# tottag.net
KiCad netlist of a schematic drawn in EAGLE
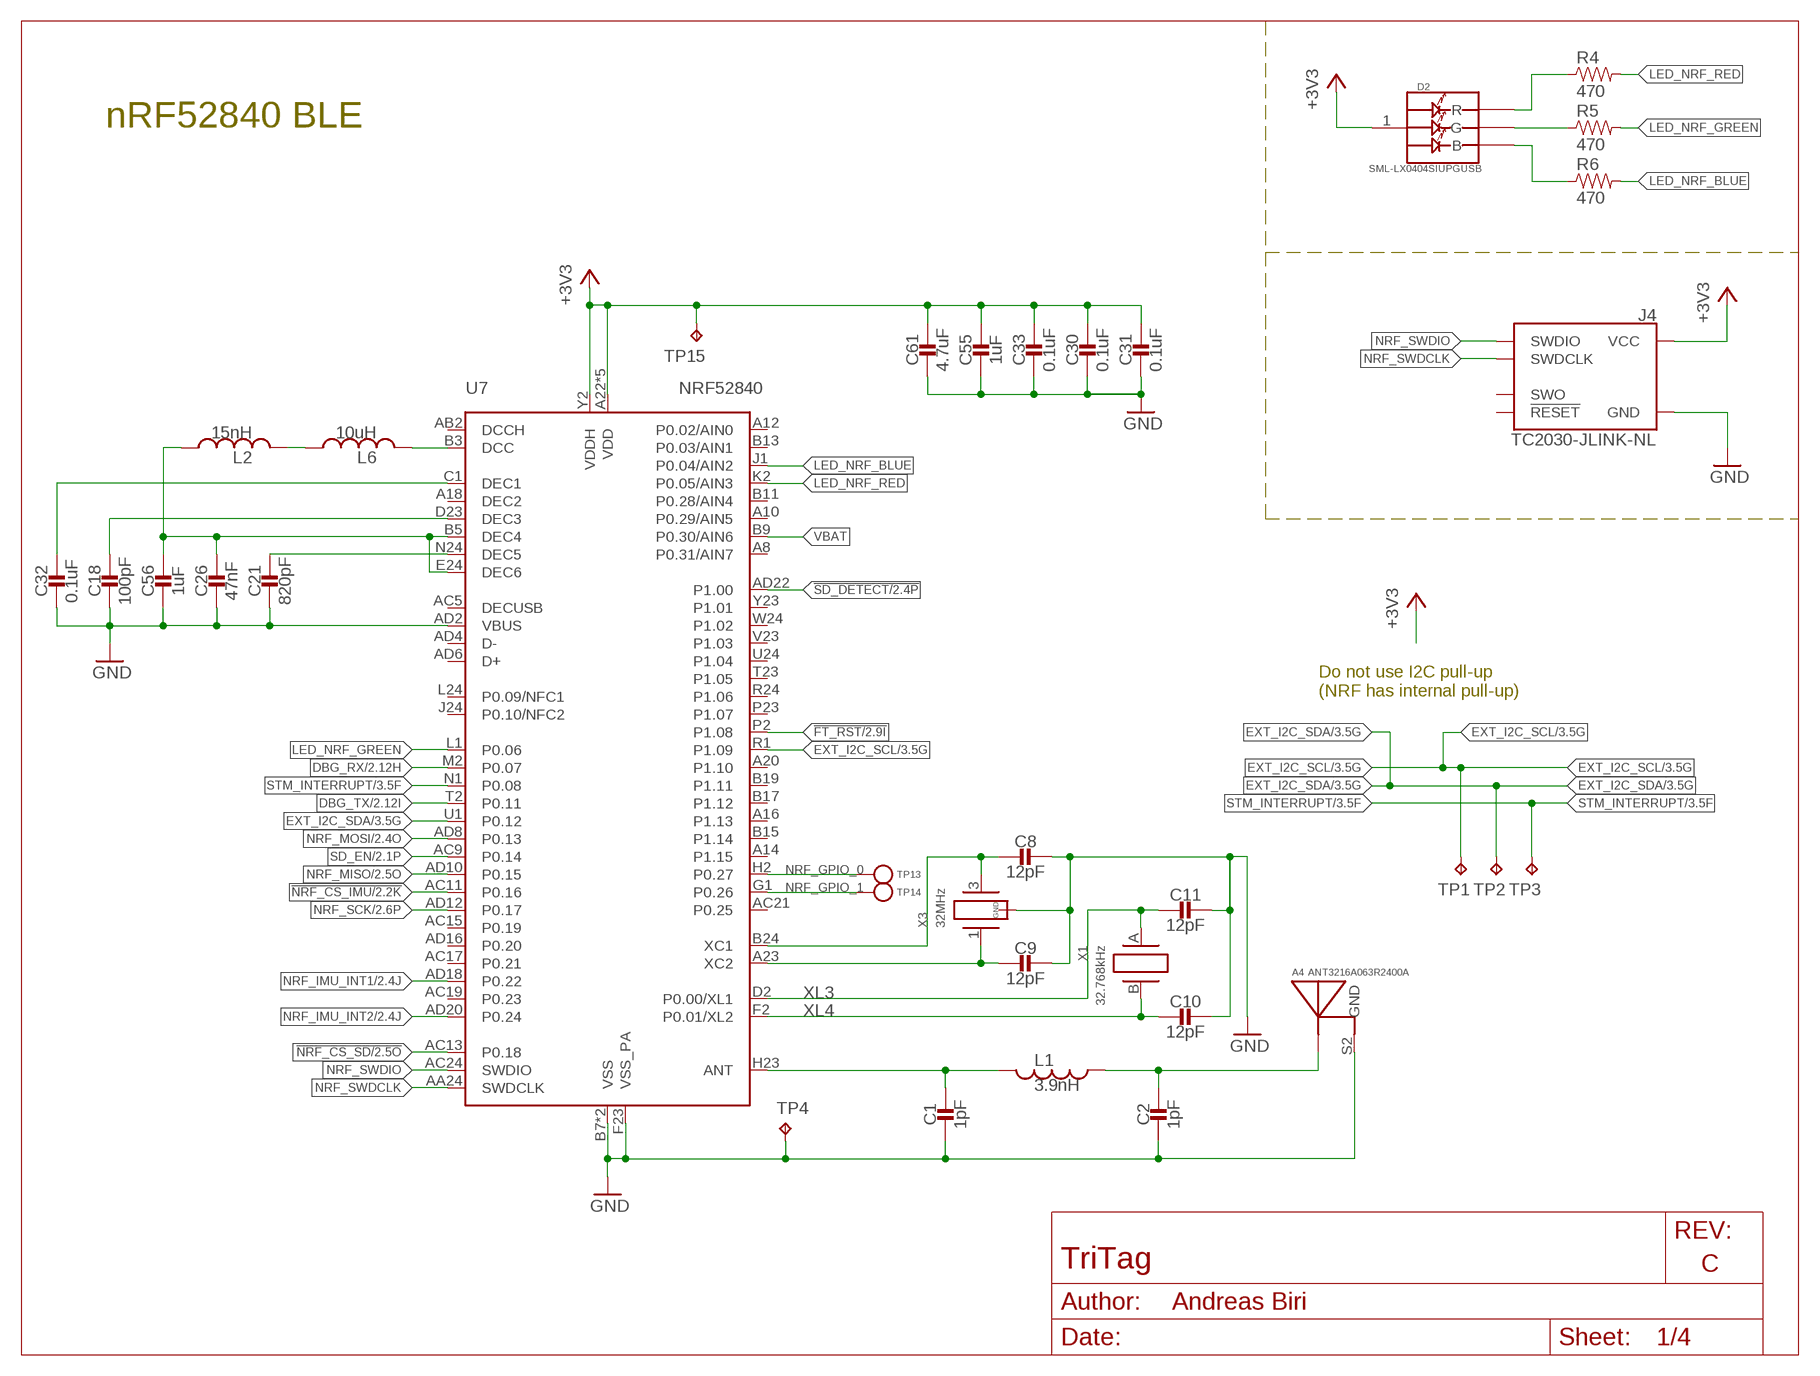
[diagram p0: schematic, sheet 1]
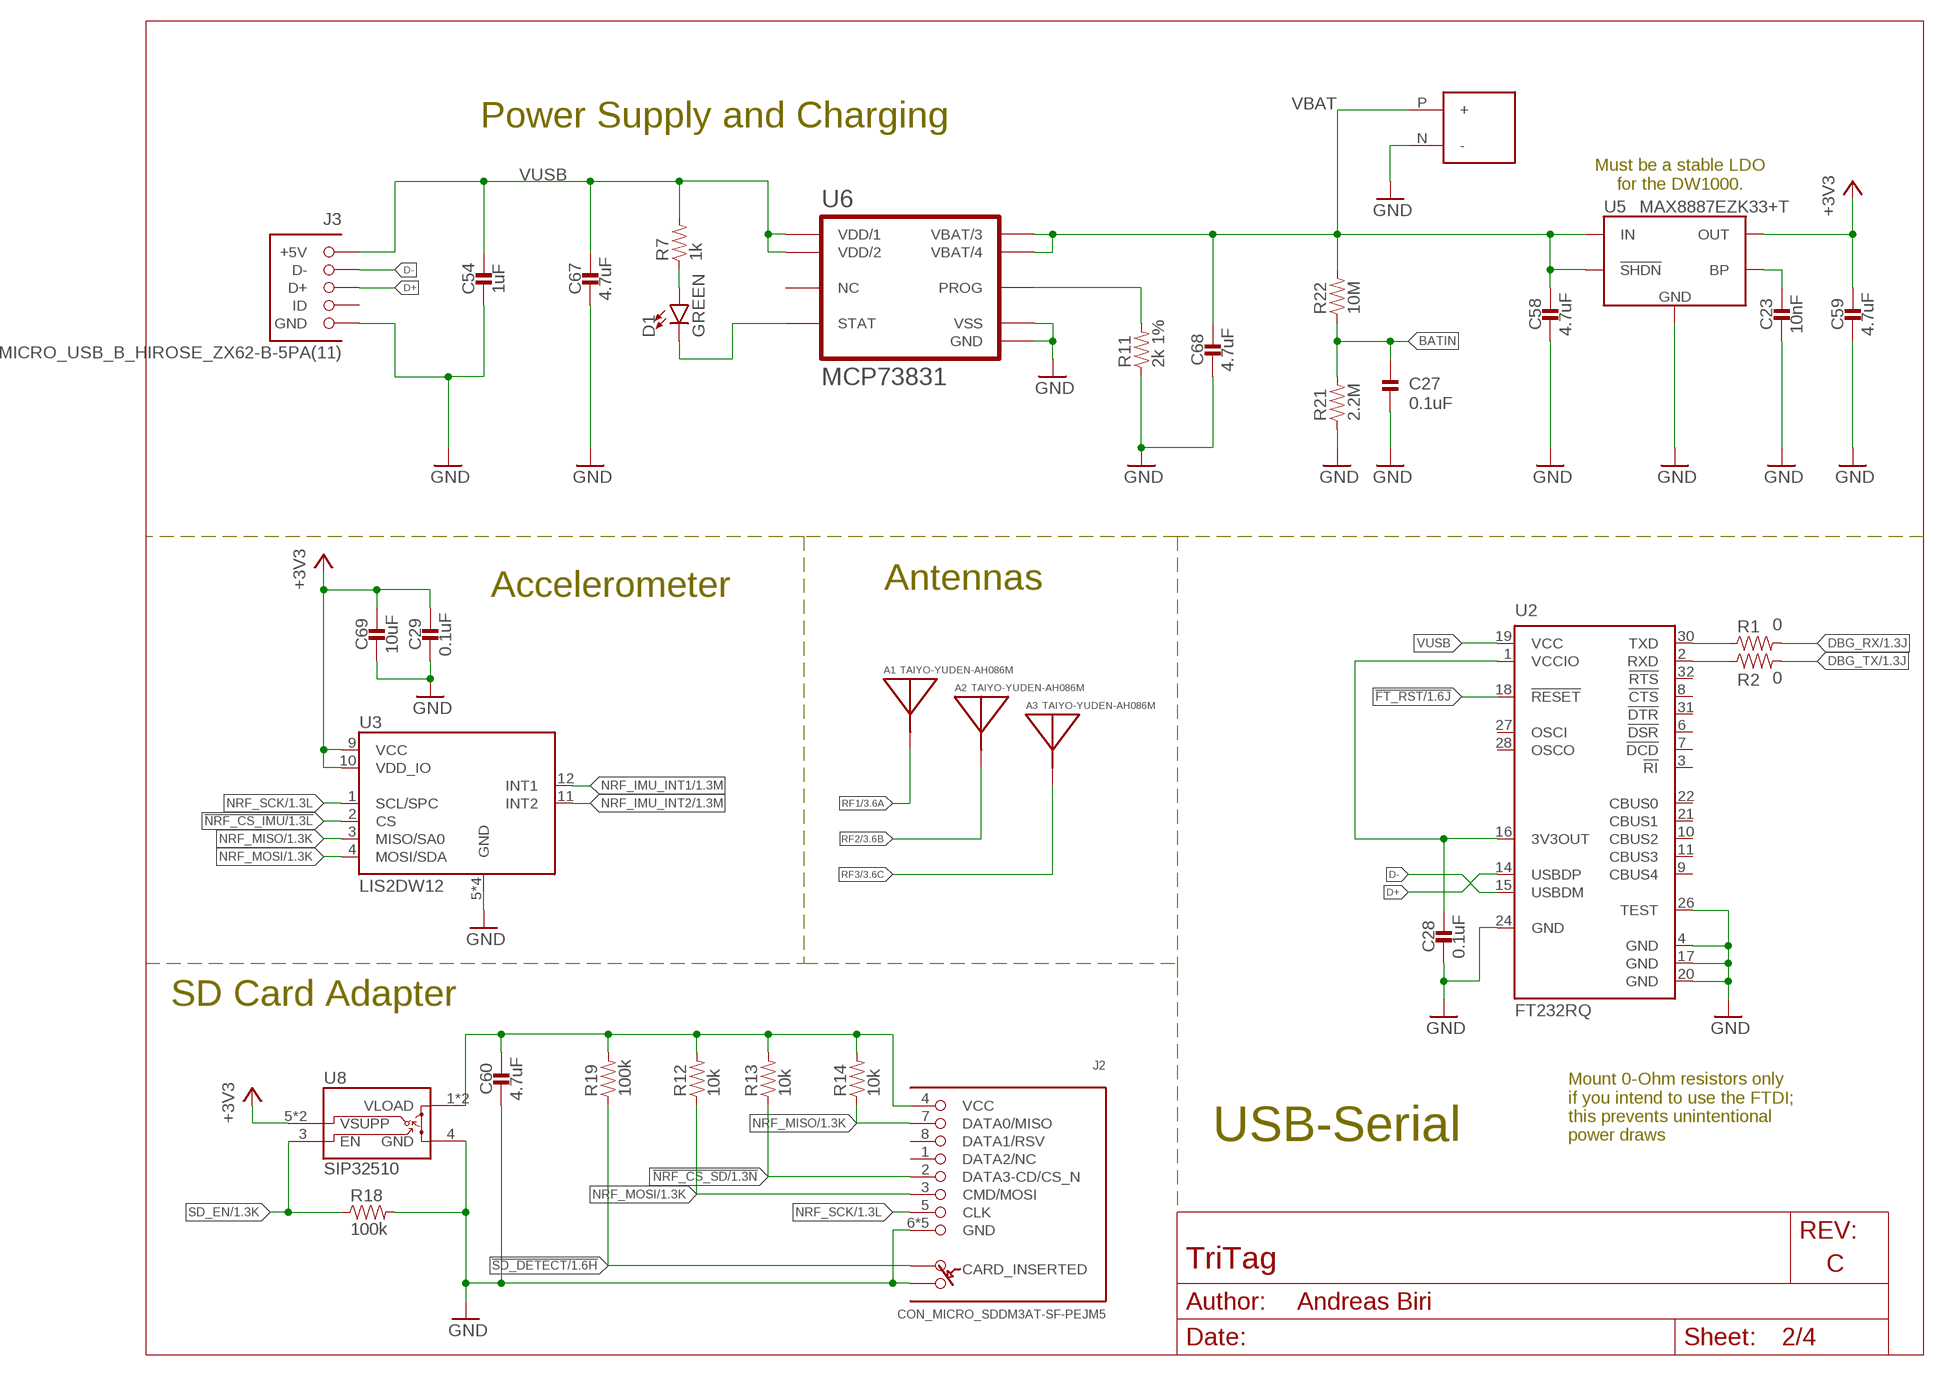
[diagram p1: schematic, sheet 2]
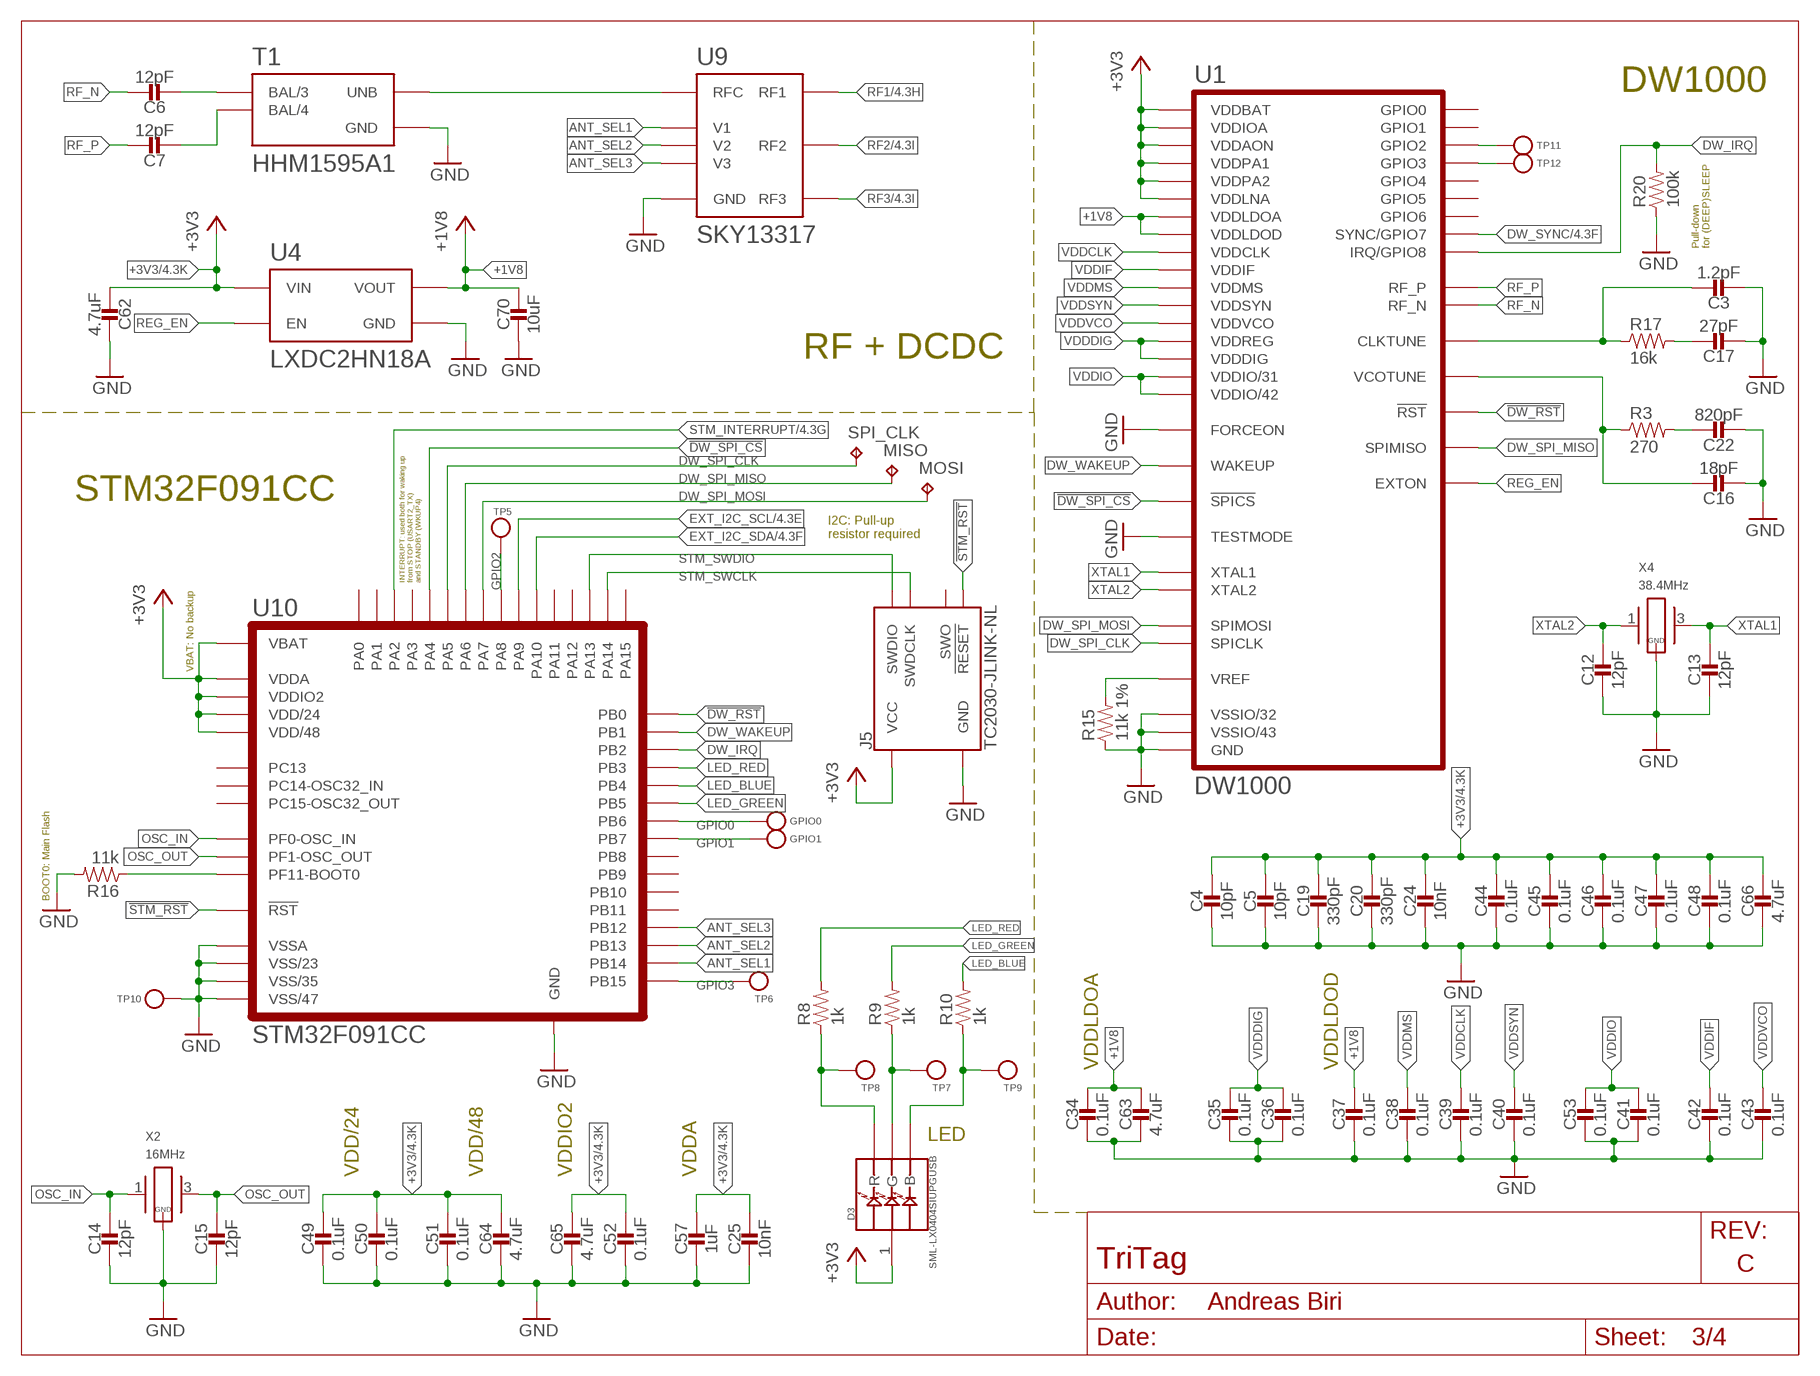
[diagram p2: schematic, sheet 3]
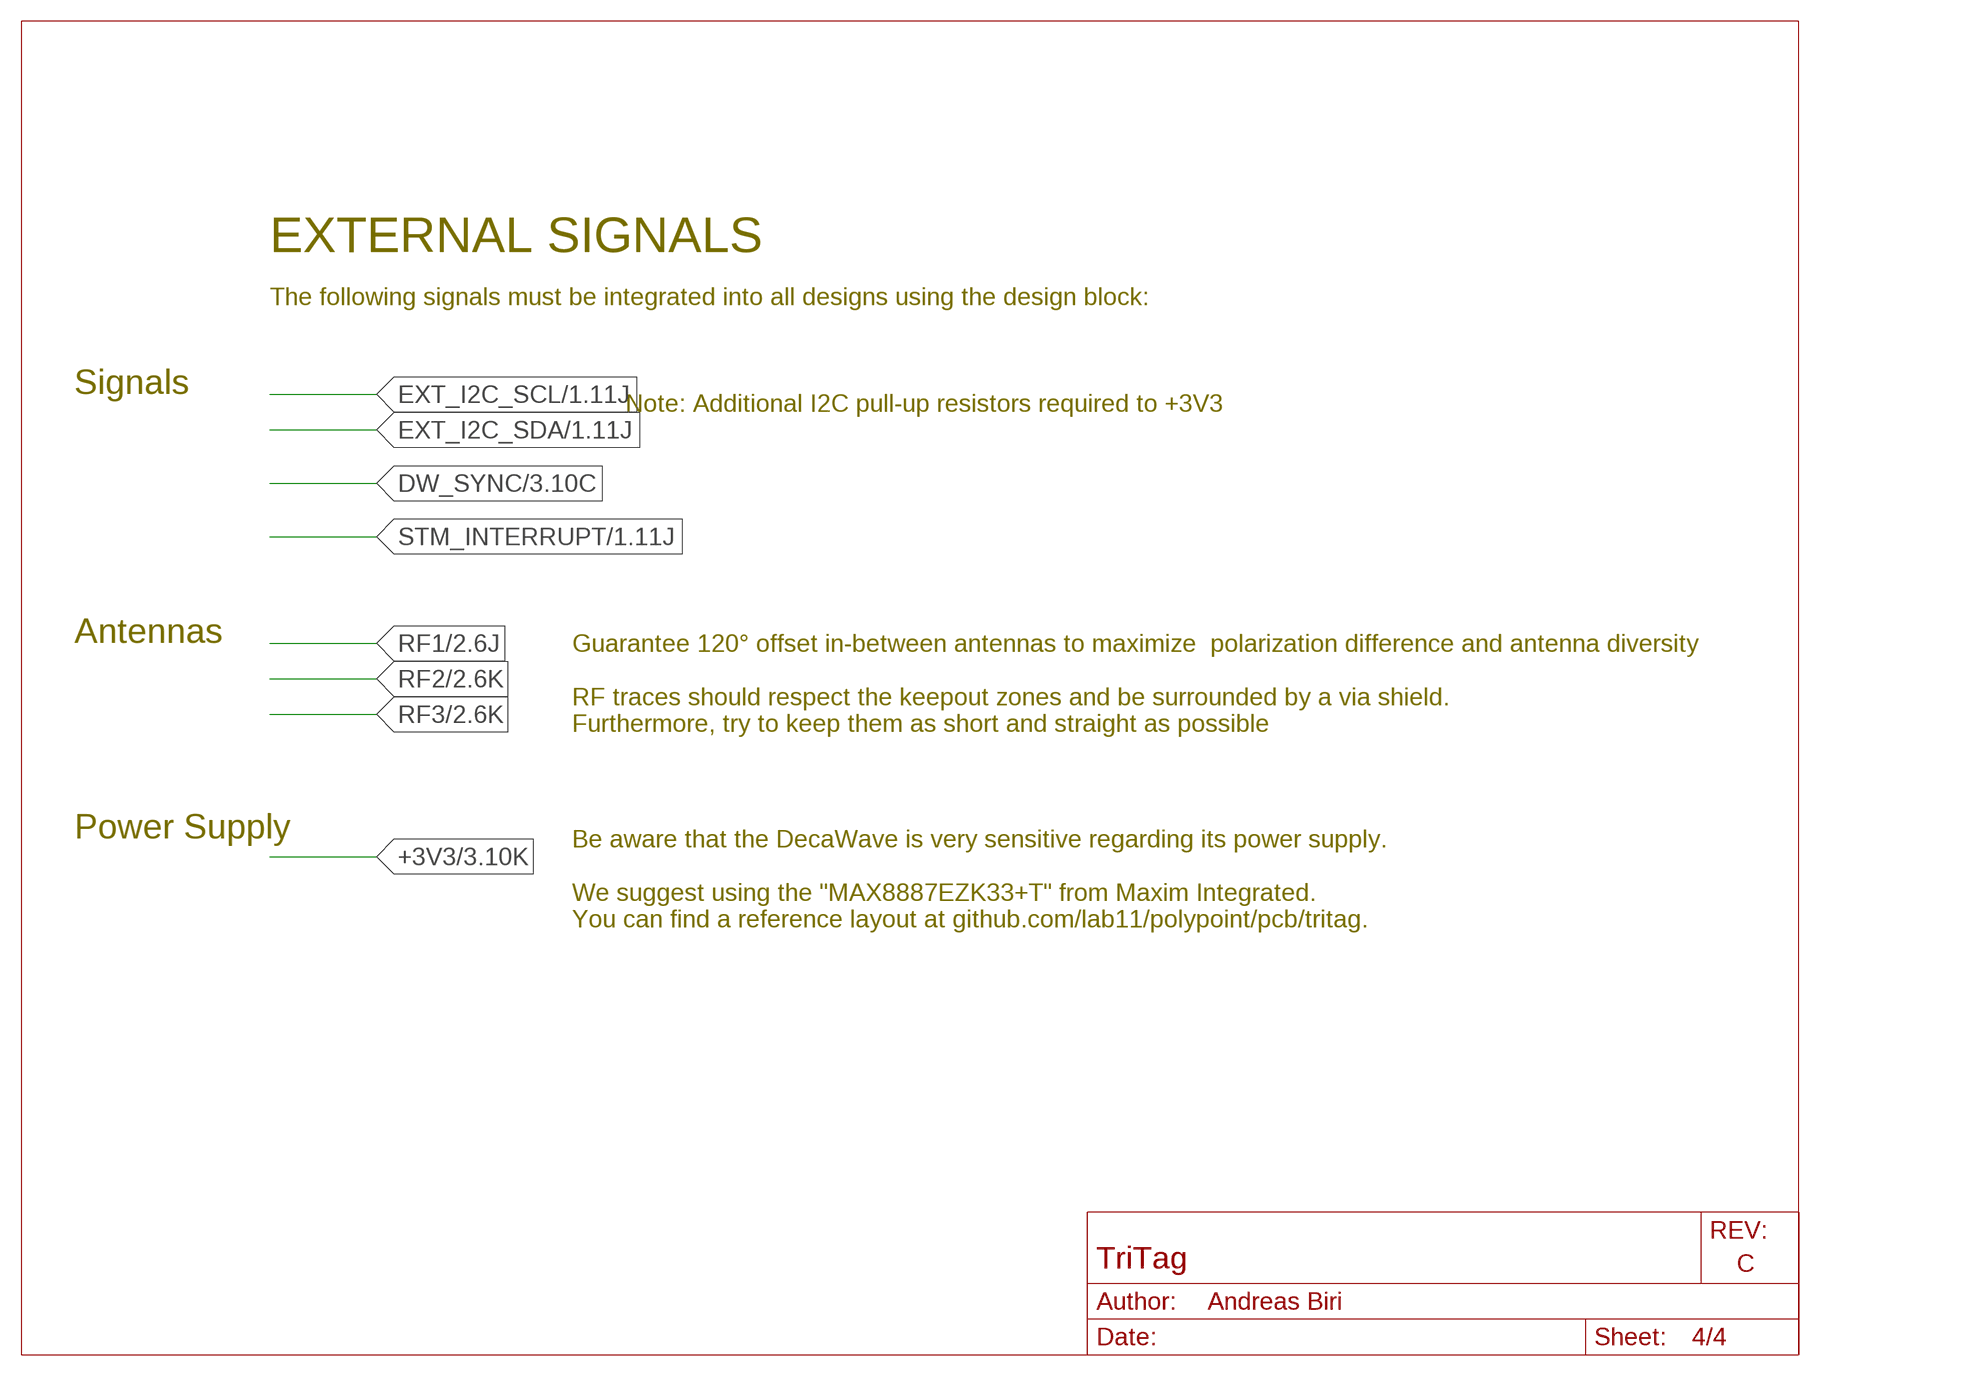
[diagram p3: schematic, sheet 4]

(export (version "E")
  (design (tool "Eeschema 10.0.6"))
  (components
    (comp (ref "A4")
      (value "ANT3216A063R2400A")
      (footprint "eagle-import:ANT3216A063R2400A")
      (fields (field (name "MANUFACTURER") "YAGEO"))
      (libsource (lib "eagle-import") (part "ANT3216A063R2400A"))
    )
    (comp (ref "C1")
      (value "1pF")
      (footprint "eagle-import:0402_CAP")
      (fields (field (name "MPN") "GJM1555C1H1R0CB01D "))
      (libsource (lib "eagle-import") (part "CAPACITOR0402_CAP"))
    )
    (comp (ref "C2")
      (value "1pF")
      (footprint "eagle-import:0402_CAP")
      (fields (field (name "MPN") "GJM1555C1H1R0CB01D"))
      (libsource (lib "eagle-import") (part "CAPACITOR0402_CAP"))
    )
    (comp (ref "C8")
      (value "12pF")
      (footprint "eagle-import:0402_CAP")
      (fields (field (name "MPN") "GRM1555C1H120GA01D "))
      (libsource (lib "eagle-import") (part "CAPACITOR0402_CAP"))
    )
    (comp (ref "C9")
      (value "12pF")
      (footprint "eagle-import:0402_CAP")
      (fields (field (name "MPN") "GRM1555C1H120GA01D "))
      (libsource (lib "eagle-import") (part "CAPACITOR0402_CAP"))
    )
    (comp (ref "C10")
      (value "12pF")
      (footprint "eagle-import:0402_CAP")
      (fields (field (name "MPN") "GRM1555C1H120GA01D "))
      (libsource (lib "eagle-import") (part "CAPACITOR0402_CAP"))
    )
    (comp (ref "C11")
      (value "12pF")
      (footprint "eagle-import:0402_CAP")
      (fields (field (name "MPN") "GRM1555C1H120GA01D "))
      (libsource (lib "eagle-import") (part "CAPACITOR0402_CAP"))
    )
    (comp (ref "C18")
      (value "100pF")
      (footprint "eagle-import:0402_CAP")
      (fields (field (name "MPN") "GRM1555C1H101JA01D "))
      (libsource (lib "eagle-import") (part "CAPACITOR0402_CAP"))
    )
    (comp (ref "C21")
      (value "820pF")
      (footprint "eagle-import:0402_CAP")
      (fields (field (name "MPN") "CL05C821JB5NFNC"))
      (libsource (lib "eagle-import") (part "CAPACITOR0402_CAP"))
    )
    (comp (ref "C26")
      (value "47nF")
      (footprint "eagle-import:0402_CAP")
      (fields (field (name "MPN") "C1005X7R1C473K050BC "))
      (libsource (lib "eagle-import") (part "CAPACITOR0402_CAP"))
    )
    (comp (ref "C30")
      (value "0.1uF")
      (footprint "eagle-import:0402_CAP")
      (fields (field (name "MPN") "GRM155R71C104KA88J "))
      (libsource (lib "eagle-import") (part "CAPACITOR0402_CAP"))
    )
    (comp (ref "C31")
      (value "0.1uF")
      (footprint "eagle-import:0402_CAP")
      (fields (field (name "MPN") "GRM155R71C104KA88J "))
      (libsource (lib "eagle-import") (part "CAPACITOR0402_CAP"))
    )
    (comp (ref "C32")
      (value "0.1uF")
      (footprint "eagle-import:0402_CAP")
      (fields (field (name "MPN") "GRM155R71C104KA88J "))
      (libsource (lib "eagle-import") (part "CAPACITOR0402_CAP"))
    )
    (comp (ref "C33")
      (value "0.1uF")
      (footprint "eagle-import:0402_CAP")
      (fields (field (name "MPN") "GRM155R71C104KA88J "))
      (libsource (lib "eagle-import") (part "CAPACITOR0402_CAP"))
    )
    (comp (ref "C55")
      (value "1uF")
      (footprint "eagle-import:0402_CAP")
      (fields (field (name "MPN") "GRM155R70G105KA12D "))
      (libsource (lib "eagle-import") (part "CAPACITOR0402_CAP"))
    )
    (comp (ref "C56")
      (value "1uF")
      (footprint "eagle-import:0402_CAP")
      (fields (field (name "MPN") "GRM155R70G105KA12D "))
      (libsource (lib "eagle-import") (part "CAPACITOR0402_CAP"))
    )
    (comp (ref "C61")
      (value "4.7uF")
      (footprint "eagle-import:0402_CAP")
      (fields (field (name "MPN") "C1005X5R0J475K050BC "))
      (libsource (lib "eagle-import") (part "CAPACITOR0402_CAP"))
    )
    (comp (ref "D2")
      (value "SML-LX0404SIUPGUSB")
      (footprint "eagle-import:1MM_SQ_4PAD")
      (fields (field (name "MANUFACTURER") "Lumex Opto"))
      (libsource (lib "eagle-import") (part "SML-LX0404SIUPGUSB"))
    )
    (comp (ref "J4")
      (value "TC2030-JLINK-NL")
      (footprint "eagle-import:TC2030-IDC-NL")
      (libsource (lib "eagle-import") (part "TC2030-JLINK-NL"))
    )
    (comp (ref "L1")
      (value "3.9nH")
      (footprint "eagle-import:0402_CAP")
      (fields (field (name "MPN") "AISC-0402-3N9G-T "))
      (libsource (lib "eagle-import") (part "INDUCTOR0402"))
    )
    (comp (ref "L2")
      (value "15nH")
      (footprint "eagle-import:0402_CAP")
      (fields (field (name "MPN") "HK100515NJ-T "))
      (libsource (lib "eagle-import") (part "INDUCTOR0402"))
    )
    (comp (ref "L6")
      (value "10uH")
      (footprint "eagle-import:0603_CAP")
      (fields (field (name "MPN") "LQM18FN100M00D "))
      (libsource (lib "eagle-import") (part "INDUCTOR0603"))
    )
    (comp (ref "R4")
      (value "470")
      (footprint "eagle-import:0402_RES")
      (libsource (lib "eagle-import") (part "RESISTOR0402_RES"))
    )
    (comp (ref "R5")
      (value "470")
      (footprint "eagle-import:0402_RES")
      (libsource (lib "eagle-import") (part "RESISTOR0402_RES"))
    )
    (comp (ref "R6")
      (value "470")
      (footprint "eagle-import:0402_RES")
      (libsource (lib "eagle-import") (part "RESISTOR0402_RES"))
    )
    (comp (ref "TP1")
      (value "TPTP06SQ")
      (footprint "eagle-import:TP06SQ")
      (libsource (lib "eagle-import") (part "TPTP06SQ"))
    )
    (comp (ref "TP2")
      (value "TPTP06SQ")
      (footprint "eagle-import:TP06SQ")
      (libsource (lib "eagle-import") (part "TPTP06SQ"))
    )
    (comp (ref "TP3")
      (value "TPTP06SQ")
      (footprint "eagle-import:TP06SQ")
      (libsource (lib "eagle-import") (part "TPTP06SQ"))
    )
    (comp (ref "TP4")
      (value "TPTP06SQ")
      (footprint "eagle-import:TP06SQ")
      (libsource (lib "eagle-import") (part "TPTP06SQ"))
    )
    (comp (ref "TP13")
      (value "TEST-POINT")
      (footprint "eagle-import:PAD.03X.03")
      (libsource (lib "eagle-import") (part "TEST-POINT"))
    )
    (comp (ref "TP14")
      (value "TEST-POINT")
      (footprint "eagle-import:PAD.03X.03")
      (libsource (lib "eagle-import") (part "TEST-POINT"))
    )
    (comp (ref "TP15")
      (value "TPTP06SQ")
      (footprint "eagle-import:TP06SQ")
      (libsource (lib "eagle-import") (part "TPTP06SQ"))
    )
    (comp (ref "U7")
      (value "NRF52840")
      (footprint "eagle-import:AQFN73")
      (fields (field (name "MANUFACTURER") "NORIDIC SEMICONDUCTOR"))
      (libsource (lib "eagle-import") (part "NRF52840"))
    )
    (comp (ref "X1")
      (value "32.768kHz")
      (footprint "eagle-import:ABS05")
      (fields (field (name "MANUFACTURER") "Abracon") (field (name "MPN") "ABS05-32.768KHZ-9-T"))
      (libsource (lib "eagle-import") (part "ABS05-32.768KHZ-9-T"))
    )
    (comp (ref "X3")
      (value "32MHz")
      (footprint "eagle-import:TXC-7V")
      (fields (field (name "MANUFACTURER") "TXC CORPORATION") (field (name "MPN") "7M-32.000MAHV-T"))
      (libsource (lib "eagle-import") (part "7V-32.000MAHV-T"))
    )
    (comp (ref "C3")
      (value "1.2pF")
      (footprint "eagle-import:0402_CAP")
      (libsource (lib "eagle-import") (part "CAPACITOR0402_CAP"))
    )
    (comp (ref "C4")
      (value "10pF")
      (footprint "eagle-import:0402_CAP")
      (libsource (lib "eagle-import") (part "CAPACITOR0402_CAP"))
    )
    (comp (ref "C5")
      (value "10pF")
      (footprint "eagle-import:0402_CAP")
      (libsource (lib "eagle-import") (part "CAPACITOR0402_CAP"))
    )
    (comp (ref "C6")
      (value "12pF")
      (footprint "eagle-import:0201_CAP")
      (libsource (lib "eagle-import") (part "CAPACITOR0201_CAP"))
    )
    (comp (ref "C7")
      (value "12pF")
      (footprint "eagle-import:0201_CAP")
      (libsource (lib "eagle-import") (part "CAPACITOR0201_CAP"))
    )
    (comp (ref "C12")
      (value "12pF")
      (footprint "eagle-import:0402_CAP")
      (libsource (lib "eagle-import") (part "CAPACITOR0402_CAP"))
    )
    (comp (ref "C13")
      (value "12pF")
      (footprint "eagle-import:0402_CAP")
      (libsource (lib "eagle-import") (part "CAPACITOR0402_CAP"))
    )
    (comp (ref "C14")
      (value "12pF")
      (footprint "eagle-import:0402_CAP")
      (libsource (lib "eagle-import") (part "CAPACITOR0402_CAP"))
    )
    (comp (ref "C15")
      (value "12pF")
      (footprint "eagle-import:0402_CAP")
      (libsource (lib "eagle-import") (part "CAPACITOR0402_CAP"))
    )
    (comp (ref "C16")
      (value "18pF")
      (footprint "eagle-import:0402_CAP")
      (libsource (lib "eagle-import") (part "CAPACITOR0402_CAP"))
    )
    (comp (ref "C17")
      (value "27pF")
      (footprint "eagle-import:0402_CAP")
      (libsource (lib "eagle-import") (part "CAPACITOR0402_CAP"))
    )
    (comp (ref "C19")
      (value "330pF")
      (footprint "eagle-import:0402_CAP")
      (libsource (lib "eagle-import") (part "CAPACITOR0402_CAP"))
    )
    (comp (ref "C20")
      (value "330pF")
      (footprint "eagle-import:0402_CAP")
      (libsource (lib "eagle-import") (part "CAPACITOR0402_CAP"))
    )
    (comp (ref "C22")
      (value "820pF")
      (footprint "eagle-import:0402_CAP")
      (libsource (lib "eagle-import") (part "CAPACITOR0402_CAP"))
    )
    (comp (ref "C24")
      (value "10nF")
      (footprint "eagle-import:0402_CAP")
      (libsource (lib "eagle-import") (part "CAPACITOR0402_CAP"))
    )
    (comp (ref "C25")
      (value "10nF")
      (footprint "eagle-import:0402_CAP")
      (libsource (lib "eagle-import") (part "CAPACITOR0402_CAP"))
    )
    (comp (ref "C34")
      (value "0.1uF")
      (footprint "eagle-import:0402_CAP")
      (libsource (lib "eagle-import") (part "CAPACITOR0402_CAP"))
    )
    (comp (ref "C35")
      (value "0.1uF")
      (footprint "eagle-import:0402_CAP")
      (libsource (lib "eagle-import") (part "CAPACITOR0402_CAP"))
    )
    (comp (ref "C36")
      (value "0.1uF")
      (footprint "eagle-import:0402_CAP")
      (libsource (lib "eagle-import") (part "CAPACITOR0402_CAP"))
    )
    (comp (ref "C37")
      (value "0.1uF")
      (footprint "eagle-import:0402_CAP")
      (libsource (lib "eagle-import") (part "CAPACITOR0402_CAP"))
    )
    (comp (ref "C38")
      (value "0.1uF")
      (footprint "eagle-import:0402_CAP")
      (libsource (lib "eagle-import") (part "CAPACITOR0402_CAP"))
    )
    (comp (ref "C39")
      (value "0.1uF")
      (footprint "eagle-import:0402_CAP")
      (libsource (lib "eagle-import") (part "CAPACITOR0402_CAP"))
    )
    (comp (ref "C40")
      (value "0.1uF")
      (footprint "eagle-import:0402_CAP")
      (libsource (lib "eagle-import") (part "CAPACITOR0402_CAP"))
    )
    (comp (ref "C41")
      (value "0.1uF")
      (footprint "eagle-import:0402_CAP")
      (libsource (lib "eagle-import") (part "CAPACITOR0402_CAP"))
    )
    (comp (ref "C42")
      (value "0.1uF")
      (footprint "eagle-import:0402_CAP")
      (libsource (lib "eagle-import") (part "CAPACITOR0402_CAP"))
    )
    (comp (ref "C43")
      (value "0.1uF")
      (footprint "eagle-import:0402_CAP")
      (libsource (lib "eagle-import") (part "CAPACITOR0402_CAP"))
    )
    (comp (ref "C44")
      (value "0.1uF")
      (footprint "eagle-import:0402_CAP")
      (libsource (lib "eagle-import") (part "CAPACITOR0402_CAP"))
    )
    (comp (ref "C45")
      (value "0.1uF")
      (footprint "eagle-import:0402_CAP")
      (libsource (lib "eagle-import") (part "CAPACITOR0402_CAP"))
    )
    (comp (ref "C46")
      (value "0.1uF")
      (footprint "eagle-import:0402_CAP")
      (libsource (lib "eagle-import") (part "CAPACITOR0402_CAP"))
    )
    (comp (ref "C47")
      (value "0.1uF")
      (footprint "eagle-import:0402_CAP")
      (libsource (lib "eagle-import") (part "CAPACITOR0402_CAP"))
    )
    (comp (ref "C48")
      (value "0.1uF")
      (footprint "eagle-import:0402_CAP")
      (libsource (lib "eagle-import") (part "CAPACITOR0402_CAP"))
    )
    (comp (ref "C49")
      (value "0.1uF")
      (footprint "eagle-import:0402_CAP")
      (libsource (lib "eagle-import") (part "CAPACITOR0402_CAP"))
    )
    (comp (ref "C50")
      (value "0.1uF")
      (footprint "eagle-import:0402_CAP")
      (libsource (lib "eagle-import") (part "CAPACITOR0402_CAP"))
    )
    (comp (ref "C51")
      (value "0.1uF")
      (footprint "eagle-import:0402_CAP")
      (libsource (lib "eagle-import") (part "CAPACITOR0402_CAP"))
    )
    (comp (ref "C52")
      (value "0.1uF")
      (footprint "eagle-import:0402_CAP")
      (libsource (lib "eagle-import") (part "CAPACITOR0402_CAP"))
    )
    (comp (ref "C53")
      (value "0.1uF")
      (footprint "eagle-import:0402_CAP")
      (libsource (lib "eagle-import") (part "CAPACITOR0402_CAP"))
    )
    (comp (ref "C57")
      (value "1uF")
      (footprint "eagle-import:0402_CAP")
      (libsource (lib "eagle-import") (part "CAPACITOR0402_CAP"))
    )
    (comp (ref "C62")
      (value "4.7uF")
      (footprint "eagle-import:0402_CAP")
      (libsource (lib "eagle-import") (part "CAPACITOR0402_CAP"))
    )
    (comp (ref "C63")
      (value "4.7uF")
      (footprint "eagle-import:0402_CAP")
      (libsource (lib "eagle-import") (part "CAPACITOR0402_CAP"))
    )
    (comp (ref "C64")
      (value "4.7uF")
      (footprint "eagle-import:0402_CAP")
      (libsource (lib "eagle-import") (part "CAPACITOR0402_CAP"))
    )
    (comp (ref "C65")
      (value "4.7uF")
      (footprint "eagle-import:0402_CAP")
      (libsource (lib "eagle-import") (part "CAPACITOR0402_CAP"))
    )
    (comp (ref "C66")
      (value "4.7uF")
      (footprint "eagle-import:0402_CAP")
      (libsource (lib "eagle-import") (part "CAPACITOR0402_CAP"))
    )
    (comp (ref "C70")
      (value "10uF")
      (footprint "eagle-import:0603_CAP")
      (libsource (lib "eagle-import") (part "CAPACITOR0603_CAP"))
    )
    (comp (ref "D3")
      (value "SML-LX0404SIUPGUSB")
      (footprint "eagle-import:1MM_SQ_4PAD")
      (fields (field (name "MANUFACTURER") "Lumex Opto"))
      (libsource (lib "eagle-import") (part "SML-LX0404SIUPGUSB"))
    )
    (comp (ref "GPIO0")
      (value "TEST-POINT")
      (footprint "eagle-import:PAD.03X.03")
      (libsource (lib "eagle-import") (part "TEST-POINT"))
    )
    (comp (ref "GPIO1")
      (value "TEST-POINT")
      (footprint "eagle-import:PAD.03X.03")
      (libsource (lib "eagle-import") (part "TEST-POINT"))
    )
    (comp (ref "J5")
      (value "TC2030-JLINK-NL")
      (footprint "eagle-import:TC2030-IDC-NL")
      (libsource (lib "eagle-import") (part "TC2030-JLINK-NL"))
    )
    (comp (ref "MISO")
      (value "TPTP06SQ")
      (footprint "eagle-import:TP06SQ")
      (libsource (lib "eagle-import") (part "TPTP06SQ"))
    )
    (comp (ref "MOSI")
      (value "TPTP06SQ")
      (footprint "eagle-import:TP06SQ")
      (libsource (lib "eagle-import") (part "TPTP06SQ"))
    )
    (comp (ref "R3")
      (value "270")
      (footprint "eagle-import:0402_RES")
      (libsource (lib "eagle-import") (part "RESISTOR0402_RES"))
    )
    (comp (ref "R8")
      (value "1k")
      (footprint "eagle-import:0402_RES")
      (libsource (lib "eagle-import") (part "RESISTOR0402_RES"))
    )
    (comp (ref "R9")
      (value "1k")
      (footprint "eagle-import:0402_RES")
      (libsource (lib "eagle-import") (part "RESISTOR0402_RES"))
    )
    (comp (ref "R10")
      (value "1k")
      (footprint "eagle-import:0402_RES")
      (libsource (lib "eagle-import") (part "RESISTOR0402_RES"))
    )
    (comp (ref "R15")
      (value "11k 1%")
      (footprint "eagle-import:0402_RES")
      (libsource (lib "eagle-import") (part "RESISTOR0402_RES"))
    )
    (comp (ref "R16")
      (value "11k")
      (footprint "eagle-import:0402_RES")
      (libsource (lib "eagle-import") (part "RESISTOR0402_RES"))
    )
    (comp (ref "R17")
      (value "16k")
      (footprint "eagle-import:0402_RES")
      (libsource (lib "eagle-import") (part "RESISTOR0402_RES"))
    )
    (comp (ref "R20")
      (value "100k")
      (footprint "eagle-import:0402_RES")
      (libsource (lib "eagle-import") (part "RESISTOR0402_RES"))
    )
    (comp (ref "SPI_CLK")
      (value "TPTP06SQ")
      (footprint "eagle-import:TP06SQ")
      (libsource (lib "eagle-import") (part "TPTP06SQ"))
    )
    (comp (ref "T1")
      (value "HHM1595A1")
      (footprint "eagle-import:EIA-0805")
      (fields (field (name "MANUFACTURER") "TDK Corporation"))
      (libsource (lib "eagle-import") (part "HHM1595A1"))
    )
    (comp (ref "TP5")
      (value "TEST-POINT")
      (footprint "eagle-import:PAD.03X.03")
      (libsource (lib "eagle-import") (part "TEST-POINT"))
    )
    (comp (ref "TP6")
      (value "TEST-POINT")
      (footprint "eagle-import:PAD.03X.03")
      (libsource (lib "eagle-import") (part "TEST-POINT"))
    )
    (comp (ref "TP7")
      (value "TEST-POINT")
      (footprint "eagle-import:PAD.03X.03")
      (libsource (lib "eagle-import") (part "TEST-POINT"))
    )
    (comp (ref "TP8")
      (value "TEST-POINT")
      (footprint "eagle-import:PAD.03X.03")
      (libsource (lib "eagle-import") (part "TEST-POINT"))
    )
    (comp (ref "TP9")
      (value "TEST-POINT")
      (footprint "eagle-import:PAD.03X.03")
      (libsource (lib "eagle-import") (part "TEST-POINT"))
    )
    (comp (ref "TP10")
      (value "TEST-POINT")
      (footprint "eagle-import:PAD.03X.03")
      (libsource (lib "eagle-import") (part "TEST-POINT"))
    )
    (comp (ref "TP11")
      (value "TEST-POINT")
      (footprint "eagle-import:PAD.03X.03")
      (libsource (lib "eagle-import") (part "TEST-POINT"))
    )
    (comp (ref "TP12")
      (value "TEST-POINT")
      (footprint "eagle-import:PAD.03X.03")
      (libsource (lib "eagle-import") (part "TEST-POINT"))
    )
    (comp (ref "U1")
      (value "DW1000")
      (footprint "eagle-import:QFN-48-DW1000")
      (fields (field (name "MANUFACTURER") "Decawave Limited") (field (name "MPN") "DW1000-I-TR13"))
      (libsource (lib "eagle-import") (part "DW1000"))
    )
    (comp (ref "U4")
      (value "LXDC2HN18A")
      (footprint "eagle-import:LXDC2HN")
      (fields
        (field (name "MANUFACTURER") "Murata Electronics North America")
        (field (name "MPN") "LXDC2HN18A-097")
      )
      (libsource (lib "eagle-import") (part "LXDC2HN18A"))
    )
    (comp (ref "U9")
      (value "SKY13317")
      (footprint "eagle-import:MLPQ-UT-8")
      (fields (field (name "MANUFACTURER") "Skyworks Solutions Inc.") (field (name "MPN") "SKY13317-373LF"))
      (libsource (lib "eagle-import") (part "SKY13317"))
    )
    (comp (ref "U10")
      (value "STM32F091CC")
      (footprint "eagle-import:UFQFPN-48")
      (fields (field (name "MANUFACTURER") "STMicroelectronics") (field (name "MPN") "STM32F091CCU6"))
      (libsource (lib "eagle-import") (part "STM32F091CC"))
    )
    (comp (ref "X2")
      (value "16MHz")
      (footprint "eagle-import:FA-20H")
      (description "16MHz ±10ppm Crystal 8pF 80 Ohms 4-SMD, No Lead")
      (fields (field (name "MANUFACTURER") "EPSON"))
      (libsource (lib "eagle-import") (part "FA-20H"))
    )
    (comp (ref "X4")
      (value "38.4MHz")
      (footprint "eagle-import:FA-20H")
      (description "38.4MHz ±10ppm Crystal 8.5pF 40 Ohms 4-SMD, No Lead")
      (fields (field (name "MANUFACTURER") "EPSON"))
      (libsource (lib "eagle-import") (part "FA-20H"))
    )
    (comp (ref "A1")
      (value "TAIYO-YUDEN-AH086M")
      (footprint "eagle-import:TAIYO-YUDEN-AH086M")
      (libsource (lib "eagle-import") (part "TAIYO-YUDEN-AH086M"))
    )
    (comp (ref "A2")
      (value "TAIYO-YUDEN-AH086M")
      (footprint "eagle-import:TAIYO-YUDEN-AH086M")
      (libsource (lib "eagle-import") (part "TAIYO-YUDEN-AH086M"))
    )
    (comp (ref "A3")
      (value "TAIYO-YUDEN-AH086M")
      (footprint "eagle-import:TAIYO-YUDEN-AH086M")
      (libsource (lib "eagle-import") (part "TAIYO-YUDEN-AH086M"))
    )
    (comp (ref "C23")
      (value "10nF")
      (footprint "eagle-import:0402_CAP")
      (libsource (lib "eagle-import") (part "CAPACITOR0402_CAP"))
    )
    (comp (ref "C27")
      (value "0.1uF")
      (footprint "eagle-import:0402_CAP")
      (libsource (lib "eagle-import") (part "CAPACITOR0402_CAP"))
    )
    (comp (ref "C28")
      (value "0.1uF")
      (footprint "eagle-import:0402_CAP")
      (fields (field (name "MPN") "GRM155R71C104KA88J "))
      (libsource (lib "eagle-import") (part "CAPACITOR0402_CAP"))
    )
    (comp (ref "C29")
      (value "0.1uF")
      (footprint "eagle-import:0402_CAP")
      (fields (field (name "MPN") "GRM155R71C104KA88J "))
      (libsource (lib "eagle-import") (part "CAPACITOR0402_CAP"))
    )
    (comp (ref "C54")
      (value "1uF")
      (footprint "eagle-import:0402_CAP")
      (libsource (lib "eagle-import") (part "CAPACITOR0402_CAP"))
    )
    (comp (ref "C58")
      (value "4.7uF")
      (footprint "eagle-import:0402_CAP")
      (libsource (lib "eagle-import") (part "CAPACITOR0402_CAP"))
    )
    (comp (ref "C59")
      (value "4.7uF")
      (footprint "eagle-import:0402_CAP")
      (libsource (lib "eagle-import") (part "CAPACITOR0402_CAP"))
    )
    (comp (ref "C60")
      (value "4.7uF")
      (footprint "eagle-import:0402_CAP")
      (description "CAP CER 4.7UF 6.3V X5R 0402")
      (fields (field (name "MANUFACTURER") "TDK") (field (name "MPN") "C1005X5R0J475K050BC"))
      (libsource (lib "eagle-import") (part "CAPACITOR0402_CAP"))
    )
    (comp (ref "C67")
      (value "4.7uF")
      (footprint "eagle-import:0402_CAP")
      (libsource (lib "eagle-import") (part "CAPACITOR0402_CAP"))
    )
    (comp (ref "C68")
      (value "4.7uF")
      (footprint "eagle-import:0402_CAP")
      (libsource (lib "eagle-import") (part "CAPACITOR0402_CAP"))
    )
    (comp (ref "C69")
      (value "10uF")
      (footprint "eagle-import:0603_CAP")
      (fields (field (name "MPN") "GRM188R60J106ME47D "))
      (libsource (lib "eagle-import") (part "CAPACITOR0603_CAP"))
    )
    (comp (ref "D1")
      (value "GREEN")
      (footprint "eagle-import:LED-0603")
      (libsource (lib "eagle-import") (part "LED0603"))
    )
    (comp (ref "J1")
      (value "BAT_HOLE")
      (footprint "eagle-import:BATTERY_HOLE")
      (libsource (lib "eagle-import") (part "BAT_HOLE"))
    )
    (comp (ref "J2")
      (value "CON_MICRO_SDDM3AT-SF-PEJM5")
      (footprint "eagle-import:DM3AT-SF-PEJM5")
      (libsource (lib "eagle-import") (part "CON_MICRO_SDDM3AT-SF-PEJM5"))
    )
    (comp (ref "J3")
      (value "MICRO_USB_B_HIROSE_ZX62-B-5PA(11)")
      (footprint "eagle-import:USB_MICRO_B-HIROSE-ZX62-B-5PA(11)")
      (libsource (lib "eagle-import") (part "MICRO_USB_B_HIROSE_ZX62-B-5PA(11)"))
    )
    (comp (ref "R1")
      (value "0")
      (footprint "eagle-import:0402_RES")
      (libsource (lib "eagle-import") (part "RESISTOR0402_RES"))
    )
    (comp (ref "R2")
      (value "0")
      (footprint "eagle-import:0402_RES")
      (libsource (lib "eagle-import") (part "RESISTOR0402_RES"))
    )
    (comp (ref "R7")
      (value "1k")
      (footprint "eagle-import:0402_RES")
      (libsource (lib "eagle-import") (part "RESISTOR0402_RES"))
    )
    (comp (ref "R11")
      (value "2k 1%")
      (footprint "eagle-import:0402_RES")
      (libsource (lib "eagle-import") (part "RESISTOR0402_RES"))
    )
    (comp (ref "R12")
      (value "10k")
      (footprint "eagle-import:0402_RES")
      (libsource (lib "eagle-import") (part "RESISTOR0402_RES"))
    )
    (comp (ref "R13")
      (value "10k")
      (footprint "eagle-import:0402_RES")
      (libsource (lib "eagle-import") (part "RESISTOR0402_RES"))
    )
    (comp (ref "R14")
      (value "10k")
      (footprint "eagle-import:0402_RES")
      (libsource (lib "eagle-import") (part "RESISTOR0402_RES"))
    )
    (comp (ref "R18")
      (value "100k")
      (footprint "eagle-import:0402_RES")
      (libsource (lib "eagle-import") (part "RESISTOR0402_RES"))
    )
    (comp (ref "R19")
      (value "100k")
      (footprint "eagle-import:0402_RES")
      (libsource (lib "eagle-import") (part "RESISTOR0402_RES"))
    )
    (comp (ref "R21")
      (value "2.2M")
      (footprint "eagle-import:0402_RES")
      (libsource (lib "eagle-import") (part "RESISTOR0402_RES"))
    )
    (comp (ref "R22")
      (value "10M")
      (footprint "eagle-import:0402_RES")
      (libsource (lib "eagle-import") (part "RESISTOR0402_RES"))
    )
    (comp (ref "U2")
      (value "FT232RQ")
      (footprint "eagle-import:QFN32")
      (libsource (lib "eagle-import") (part "FT232RQ"))
    )
    (comp (ref "U3")
      (value "LIS2DW12")
      (footprint "eagle-import:LGA-12")
      (fields (field (name "MANUFACTURER") "STMicroelectronics") (field (name "MPN") "LIS2DW12TR"))
      (libsource (lib "eagle-import") (part "LIS2DW12"))
    )
    (comp (ref "U5")
      (value "MAX8887EZK33+T")
      (footprint "eagle-import:SOT-23-5")
      (libsource (lib "eagle-import") (part "MAX8887EZK33+T"))
    )
    (comp (ref "U6")
      (value "MCP73831")
      (footprint "eagle-import:DFN-8-MCP")
      (fields (field (name "MANUFACTURER") "Microchip Technology") (field (name "MPN") "MCP73831T-2ACI/MC"))
      (libsource (lib "eagle-import") (part "MCP73831"))
    )
    (comp (ref "U8")
      (value "SIP32510")
      (footprint "eagle-import:TSOT23-6")
      (fields (field (name "MANUFACTURER") "Vishay") (field (name "MPN") "SIP32510DT-T1-GE3"))
      (libsource (lib "eagle-import") (part "SIP32510"))
    )
  )
  (nets
    (net (code "1") (name "+1V8") (class "Default")
      (node (ref "C34") (pin "1") (pinfunction "1_1") (pintype "bidirectional"))
      (node (ref "C37") (pin "1") (pinfunction "1_1") (pintype "bidirectional"))
      (node (ref "C63") (pin "1") (pinfunction "1_1") (pintype "bidirectional"))
      (node (ref "C70") (pin "1") (pinfunction "1_1") (pintype "bidirectional"))
      (node (ref "U1") (pin "26") (pinfunction "VDDLDOD_26") (pintype "power_in"))
      (node (ref "U1") (pin "48") (pinfunction "VDDLDOA_48") (pintype "power_in"))
      (node (ref "U4") (pin "3") (pinfunction "VOUT_3") (pintype "power_in"))
    )
    (net (code "2") (name "+3V3") (class "Default")
      (node (ref "C19") (pin "1") (pinfunction "1_1") (pintype "bidirectional"))
      (node (ref "C20") (pin "1") (pinfunction "1_1") (pintype "bidirectional"))
      (node (ref "C24") (pin "1") (pinfunction "1_1") (pintype "bidirectional"))
      (node (ref "C25") (pin "1") (pinfunction "1_1") (pintype "bidirectional"))
      (node (ref "C29") (pin "1") (pinfunction "1_1") (pintype "bidirectional"))
      (node (ref "C30") (pin "1") (pinfunction "1_1") (pintype "bidirectional"))
      (node (ref "C31") (pin "1") (pinfunction "1_1") (pintype "bidirectional"))
      (node (ref "C33") (pin "1") (pinfunction "1_1") (pintype "bidirectional"))
      (node (ref "C4") (pin "1") (pinfunction "1_1") (pintype "bidirectional"))
      (node (ref "C44") (pin "1") (pinfunction "1_1") (pintype "bidirectional"))
      (node (ref "C45") (pin "1") (pinfunction "1_1") (pintype "bidirectional"))
      (node (ref "C46") (pin "1") (pinfunction "1_1") (pintype "bidirectional"))
      (node (ref "C47") (pin "1") (pinfunction "1_1") (pintype "bidirectional"))
      (node (ref "C48") (pin "1") (pinfunction "1_1") (pintype "bidirectional"))
      (node (ref "C49") (pin "1") (pinfunction "1_1") (pintype "bidirectional"))
      (node (ref "C5") (pin "1") (pinfunction "1_1") (pintype "bidirectional"))
      (node (ref "C50") (pin "1") (pinfunction "1_1") (pintype "bidirectional"))
      (node (ref "C51") (pin "1") (pinfunction "1_1") (pintype "bidirectional"))
      (node (ref "C52") (pin "1") (pinfunction "1_1") (pintype "bidirectional"))
      (node (ref "C55") (pin "1") (pinfunction "1_1") (pintype "bidirectional"))
      (node (ref "C57") (pin "1") (pinfunction "1_1") (pintype "bidirectional"))
      (node (ref "C59") (pin "1") (pinfunction "1_1") (pintype "bidirectional"))
      (node (ref "C61") (pin "1") (pinfunction "1_1") (pintype "bidirectional"))
      (node (ref "C62") (pin "2") (pinfunction "2_2") (pintype "bidirectional"))
      (node (ref "C64") (pin "1") (pinfunction "1_1") (pintype "bidirectional"))
      (node (ref "C65") (pin "1") (pinfunction "1_1") (pintype "bidirectional"))
      (node (ref "C66") (pin "1") (pinfunction "1_1") (pintype "bidirectional"))
      (node (ref "C69") (pin "1") (pinfunction "1_1") (pintype "bidirectional"))
      (node (ref "D2") (pin "1") (pinfunction "VDD_1") (pintype "bidirectional"))
      (node (ref "D3") (pin "1") (pinfunction "VDD_1") (pintype "bidirectional"))
      (node (ref "J4") (pin "1") (pinfunction "VCC_1") (pintype "bidirectional"))
      (node (ref "J5") (pin "1") (pinfunction "VCC_1") (pintype "bidirectional"))
      (node (ref "TP15") (pin "TP") (pinfunction "TP_TP") (pintype "input"))
      (node (ref "U1") (pin "15") (pinfunction "VDDLNA_15") (pintype "power_in"))
      (node (ref "U1") (pin "18") (pinfunction "VDDPA1_18") (pintype "power_in"))
      (node (ref "U1") (pin "19") (pinfunction "VDDPA2_19") (pintype "power_in"))
      (node (ref "U1") (pin "25") (pinfunction "VDDAON_25") (pintype "power_in"))
      (node (ref "U1") (pin "28") (pinfunction "VDDIOA_28") (pintype "power_in"))
      (node (ref "U1") (pin "47") (pinfunction "VDDBAT_47") (pintype "power_in"))
      (node (ref "U10") (pin "1") (pinfunction "VBAT_1") (pintype "power_in"))
      (node (ref "U10") (pin "24") (pinfunction "VDD/24_24") (pintype "power_in"))
      (node (ref "U10") (pin "36") (pinfunction "VDDIO2_36") (pintype "power_in"))
      (node (ref "U10") (pin "48") (pinfunction "VDD/48_48") (pintype "power_in"))
      (node (ref "U10") (pin "9") (pinfunction "VDDA_9") (pintype "power_in"))
      (node (ref "U3") (pin "10") (pinfunction "VDD_IO_10") (pintype "bidirectional"))
      (node (ref "U3") (pin "9") (pinfunction "VCC_9") (pintype "bidirectional"))
      (node (ref "U4") (pin "1") (pinfunction "VIN_1") (pintype "power_in"))
      (node (ref "U5") (pin "5") (pinfunction "OUT_5") (pintype "bidirectional"))
      (node (ref "U7") (pin "A22") (pinfunction "VDD_A22") (pintype "bidirectional"))
      (node (ref "U7") (pin "AD14") (pinfunction "VDD_AD14") (pintype "bidirectional"))
      (node (ref "U7") (pin "AD23") (pinfunction "VDD_AD23") (pintype "bidirectional"))
      (node (ref "U7") (pin "B1") (pinfunction "VDD_B1") (pintype "bidirectional"))
      (node (ref "U7") (pin "W1") (pinfunction "VDD_W1") (pintype "bidirectional"))
      (node (ref "U7") (pin "Y2") (pinfunction "VDDH_Y2") (pintype "bidirectional"))
      (node (ref "U8") (pin "5") (pinfunction "VSUPP_5") (pintype "bidirectional"))
      (node (ref "U8") (pin "6") (pinfunction "VSUPP_6") (pintype "bidirectional"))
    )
    (net (code "3") (name "ANT_SEL1") (class "Default")
      (node (ref "U10") (pin "27") (pinfunction "PB14_27") (pintype "bidirectional"))
      (node (ref "U9") (pin "3") (pinfunction "V1_3") (pintype "bidirectional"))
    )
    (net (code "4") (name "ANT_SEL2") (class "Default")
      (node (ref "U10") (pin "26") (pinfunction "PB13_26") (pintype "bidirectional"))
      (node (ref "U9") (pin "6") (pinfunction "V2_6") (pintype "bidirectional"))
    )
    (net (code "5") (name "ANT_SEL3") (class "Default")
      (node (ref "U10") (pin "25") (pinfunction "PB12_25") (pintype "bidirectional"))
      (node (ref "U9") (pin "7") (pinfunction "V3_7") (pintype "bidirectional"))
    )
    (net (code "6") (name "BATIN") (class "Default")
      (node (ref "C27") (pin "2") (pinfunction "2_2") (pintype "bidirectional"))
      (node (ref "R21") (pin "2") (pinfunction "2_2") (pintype "passive"))
      (node (ref "R22") (pin "1") (pinfunction "1_1") (pintype "passive"))
    )
    (net (code "7") (name "D+") (class "Default")
      (node (ref "J3") (pin "3") (pinfunction "D+_3") (pintype "bidirectional"))
      (node (ref "U2") (pin "14") (pinfunction "USBDP_14") (pintype "bidirectional"))
    )
    (net (code "8") (name "D-") (class "Default")
      (node (ref "J3") (pin "2") (pinfunction "D-_2") (pintype "bidirectional"))
      (node (ref "U2") (pin "15") (pinfunction "USBDM_15") (pintype "bidirectional"))
    )
    (net (code "9") (name "DBG_RX") (class "Default")
      (node (ref "R1") (pin "2") (pinfunction "2_2") (pintype "passive"))
      (node (ref "U7") (pin "M2") (pinfunction "P0.07_M2") (pintype "bidirectional"))
    )
    (net (code "10") (name "DBG_TX") (class "Default")
      (node (ref "R2") (pin "2") (pinfunction "2_2") (pintype "passive"))
      (node (ref "U7") (pin "T2") (pinfunction "P0.11_T2") (pintype "bidirectional"))
    )
    (net (code "11") (name "DW_IRQ") (class "Default")
      (node (ref "R20") (pin "2") (pinfunction "2_2") (pintype "passive"))
      (node (ref "U1") (pin "45") (pinfunction "IRQ/GPIO8_45") (pintype "bidirectional"))
      (node (ref "U10") (pin "20") (pinfunction "PB2_20") (pintype "bidirectional"))
    )
    (net (code "12") (name "DW_SPI_CLK") (class "Default")
      (node (ref "SPI_CLK") (pin "TP") (pinfunction "TP_TP") (pintype "input"))
      (node (ref "U1") (pin "41") (pinfunction "SPICLK_41") (pintype "input"))
      (node (ref "U10") (pin "15") (pinfunction "PA5_15") (pintype "bidirectional"))
    )
    (net (code "13") (name "DW_SPI_MISO") (class "Default")
      (node (ref "MISO") (pin "TP") (pinfunction "TP_TP") (pintype "input"))
      (node (ref "U1") (pin "40") (pinfunction "SPIMISO_40") (pintype "output"))
      (node (ref "U10") (pin "16") (pinfunction "PA6_16") (pintype "bidirectional"))
    )
    (net (code "14") (name "DW_SPI_MOSI") (class "Default")
      (node (ref "MOSI") (pin "TP") (pinfunction "TP_TP") (pintype "input"))
      (node (ref "U1") (pin "39") (pinfunction "SPIMOSI_39") (pintype "input"))
      (node (ref "U10") (pin "17") (pinfunction "PA7_17") (pintype "bidirectional"))
    )
    (net (code "15") (name "DW_SYNC") (class "Default")
      (node (ref "U1") (pin "29") (pinfunction "SYNC/GPIO7_29") (pintype "bidirectional"))
    )
    (net (code "16") (name "DW_WAKEUP") (class "Default")
      (node (ref "U1") (pin "23") (pinfunction "WAKEUP_23") (pintype "input"))
      (node (ref "U10") (pin "19") (pinfunction "PB1_19") (pintype "bidirectional"))
    )
    (net (code "17") (name "EXT_I2C_SCL") (class "Default")
      (node (ref "TP1") (pin "TP") (pinfunction "TP_TP") (pintype "input"))
      (node (ref "U10") (pin "30") (pinfunction "PA9_30") (pintype "bidirectional"))
      (node (ref "U7") (pin "R1") (pinfunction "P1.09_R1") (pintype "bidirectional"))
    )
    (net (code "18") (name "EXT_I2C_SDA") (class "Default")
      (node (ref "TP2") (pin "TP") (pinfunction "TP_TP") (pintype "input"))
      (node (ref "U10") (pin "31") (pinfunction "PA10_31") (pintype "bidirectional"))
      (node (ref "U7") (pin "U1") (pinfunction "P0.12_U1") (pintype "bidirectional"))
    )
    (net (code "19") (name "GND") (class "Default")
      (node (ref "A4") (pin "S2") (pinfunction "GND_S2") (pintype "bidirectional"))
      (node (ref "C1") (pin "2") (pinfunction "2_2") (pintype "bidirectional"))
      (node (ref "C10") (pin "1") (pinfunction "1_1") (pintype "bidirectional"))
      (node (ref "C11") (pin "1") (pinfunction "1_1") (pintype "bidirectional"))
      (node (ref "C12") (pin "2") (pinfunction "2_2") (pintype "bidirectional"))
      (node (ref "C13") (pin "2") (pinfunction "2_2") (pintype "bidirectional"))
      (node (ref "C14") (pin "2") (pinfunction "2_2") (pintype "bidirectional"))
      (node (ref "C15") (pin "2") (pinfunction "2_2") (pintype "bidirectional"))
      (node (ref "C16") (pin "2") (pinfunction "2_2") (pintype "bidirectional"))
      (node (ref "C17") (pin "2") (pinfunction "2_2") (pintype "bidirectional"))
      (node (ref "C18") (pin "2") (pinfunction "2_2") (pintype "bidirectional"))
      (node (ref "C19") (pin "2") (pinfunction "2_2") (pintype "bidirectional"))
      (node (ref "C2") (pin "2") (pinfunction "2_2") (pintype "bidirectional"))
      (node (ref "C20") (pin "2") (pinfunction "2_2") (pintype "bidirectional"))
      (node (ref "C21") (pin "2") (pinfunction "2_2") (pintype "bidirectional"))
      (node (ref "C22") (pin "2") (pinfunction "2_2") (pintype "bidirectional"))
      (node (ref "C23") (pin "2") (pinfunction "2_2") (pintype "bidirectional"))
      (node (ref "C24") (pin "2") (pinfunction "2_2") (pintype "bidirectional"))
      (node (ref "C25") (pin "2") (pinfunction "2_2") (pintype "bidirectional"))
      (node (ref "C26") (pin "2") (pinfunction "2_2") (pintype "bidirectional"))
      (node (ref "C27") (pin "1") (pinfunction "1_1") (pintype "bidirectional"))
      (node (ref "C28") (pin "2") (pinfunction "2_2") (pintype "bidirectional"))
      (node (ref "C29") (pin "2") (pinfunction "2_2") (pintype "bidirectional"))
      (node (ref "C3") (pin "2") (pinfunction "2_2") (pintype "bidirectional"))
      (node (ref "C30") (pin "2") (pinfunction "2_2") (pintype "bidirectional"))
      (node (ref "C31") (pin "2") (pinfunction "2_2") (pintype "bidirectional"))
      (node (ref "C32") (pin "2") (pinfunction "2_2") (pintype "bidirectional"))
      (node (ref "C33") (pin "2") (pinfunction "2_2") (pintype "bidirectional"))
      (node (ref "C34") (pin "2") (pinfunction "2_2") (pintype "bidirectional"))
      (node (ref "C35") (pin "2") (pinfunction "2_2") (pintype "bidirectional"))
      (node (ref "C36") (pin "2") (pinfunction "2_2") (pintype "bidirectional"))
      (node (ref "C37") (pin "2") (pinfunction "2_2") (pintype "bidirectional"))
      (node (ref "C38") (pin "2") (pinfunction "2_2") (pintype "bidirectional"))
      (node (ref "C39") (pin "2") (pinfunction "2_2") (pintype "bidirectional"))
      (node (ref "C4") (pin "2") (pinfunction "2_2") (pintype "bidirectional"))
      (node (ref "C40") (pin "2") (pinfunction "2_2") (pintype "bidirectional"))
      (node (ref "C41") (pin "2") (pinfunction "2_2") (pintype "bidirectional"))
      (node (ref "C42") (pin "2") (pinfunction "2_2") (pintype "bidirectional"))
      (node (ref "C43") (pin "2") (pinfunction "2_2") (pintype "bidirectional"))
      (node (ref "C44") (pin "2") (pinfunction "2_2") (pintype "bidirectional"))
      (node (ref "C45") (pin "2") (pinfunction "2_2") (pintype "bidirectional"))
      (node (ref "C46") (pin "2") (pinfunction "2_2") (pintype "bidirectional"))
      (node (ref "C47") (pin "2") (pinfunction "2_2") (pintype "bidirectional"))
      (node (ref "C48") (pin "2") (pinfunction "2_2") (pintype "bidirectional"))
      (node (ref "C49") (pin "2") (pinfunction "2_2") (pintype "bidirectional"))
      (node (ref "C5") (pin "2") (pinfunction "2_2") (pintype "bidirectional"))
      (node (ref "C50") (pin "2") (pinfunction "2_2") (pintype "bidirectional"))
      (node (ref "C51") (pin "2") (pinfunction "2_2") (pintype "bidirectional"))
      (node (ref "C52") (pin "2") (pinfunction "2_2") (pintype "bidirectional"))
      (node (ref "C53") (pin "2") (pinfunction "2_2") (pintype "bidirectional"))
      (node (ref "C54") (pin "2") (pinfunction "2_2") (pintype "bidirectional"))
      (node (ref "C55") (pin "2") (pinfunction "2_2") (pintype "bidirectional"))
      (node (ref "C56") (pin "2") (pinfunction "2_2") (pintype "bidirectional"))
      (node (ref "C57") (pin "2") (pinfunction "2_2") (pintype "bidirectional"))
      (node (ref "C58") (pin "2") (pinfunction "2_2") (pintype "bidirectional"))
      (node (ref "C59") (pin "2") (pinfunction "2_2") (pintype "bidirectional"))
      (node (ref "C60") (pin "2") (pinfunction "2_2") (pintype "bidirectional"))
      (node (ref "C61") (pin "2") (pinfunction "2_2") (pintype "bidirectional"))
      (node (ref "C62") (pin "1") (pinfunction "1_1") (pintype "bidirectional"))
      (node (ref "C63") (pin "2") (pinfunction "2_2") (pintype "bidirectional"))
      (node (ref "C64") (pin "2") (pinfunction "2_2") (pintype "bidirectional"))
      (node (ref "C65") (pin "2") (pinfunction "2_2") (pintype "bidirectional"))
      (node (ref "C66") (pin "2") (pinfunction "2_2") (pintype "bidirectional"))
      (node (ref "C67") (pin "2") (pinfunction "2_2") (pintype "bidirectional"))
      (node (ref "C68") (pin "2") (pinfunction "2_2") (pintype "bidirectional"))
      (node (ref "C69") (pin "2") (pinfunction "2_2") (pintype "bidirectional"))
      (node (ref "C70") (pin "2") (pinfunction "2_2") (pintype "bidirectional"))
      (node (ref "C8") (pin "1") (pinfunction "1_1") (pintype "bidirectional"))
      (node (ref "C9") (pin "1") (pinfunction "1_1") (pintype "bidirectional"))
      (node (ref "J1") (pin "N") (pinfunction "-_N") (pintype "bidirectional"))
      (node (ref "J2") (pin "6") (pinfunction "GND_6") (pintype "bidirectional"))
      (node (ref "J2") (pin "B") (pinfunction "B_B") (pintype "bidirectional"))
      (node (ref "J2") (pin "MOUNT0") (pinfunction "GND_MOUNT0") (pintype "bidirectional"))
      (node (ref "J2") (pin "MOUNT1") (pinfunction "GND_MOUNT1") (pintype "bidirectional"))
      (node (ref "J2") (pin "MOUNT2") (pinfunction "GND_MOUNT2") (pintype "bidirectional"))
      (node (ref "J2") (pin "MOUNT3") (pinfunction "GND_MOUNT3") (pintype "bidirectional"))
      (node (ref "J3") (pin "5") (pinfunction "GND_5") (pintype "bidirectional"))
      (node (ref "J4") (pin "5") (pinfunction "GND_5") (pintype "bidirectional"))
      (node (ref "J5") (pin "5") (pinfunction "GND_5") (pintype "bidirectional"))
      (node (ref "R11") (pin "1") (pinfunction "1_1") (pintype "passive"))
      (node (ref "R15") (pin "1") (pinfunction "1_1") (pintype "passive"))
      (node (ref "R16") (pin "2") (pinfunction "2_2") (pintype "passive"))
      (node (ref "R18") (pin "2") (pinfunction "2_2") (pintype "passive"))
      (node (ref "R20") (pin "1") (pinfunction "1_1") (pintype "passive"))
      (node (ref "R21") (pin "1") (pinfunction "1_1") (pintype "passive"))
      (node (ref "T1") (pin "2") (pinfunction "GND_2") (pintype "power_in"))
      (node (ref "T1") (pin "5") (pinfunction "GND_5") (pintype "power_in"))
      (node (ref "TP10") (pin "P$1") (pinfunction "TESTPOINT_P$1") (pintype "bidirectional"))
      (node (ref "TP4") (pin "TP") (pinfunction "TP_TP") (pintype "input"))
      (node (ref "U1") (pin "22") (pinfunction "FORCEON_22") (pintype "input"))
      (node (ref "U1") (pin "32") (pinfunction "VSSIO/32_32") (pintype "bidirectional"))
      (node (ref "U1") (pin "43") (pinfunction "VSSIO/43_43") (pintype "bidirectional"))
      (node (ref "U1") (pin "46") (pinfunction "TESTMODE_46") (pintype "input"))
      (node (ref "U1") (pin "GND") (pinfunction "GND_GND") (pintype "power_in"))
      (node (ref "U10") (pin "23") (pinfunction "VSS/23_23") (pintype "power_in"))
      (node (ref "U10") (pin "35") (pinfunction "VSS/35_35") (pintype "power_in"))
      (node (ref "U10") (pin "47") (pinfunction "VSS/47_47") (pintype "power_in"))
      (node (ref "U10") (pin "8") (pinfunction "VSSA_8") (pintype "power_in"))
      (node (ref "U10") (pin "GND") (pinfunction "GND_GND") (pintype "power_in"))
      (node (ref "U2") (pin "17") (pinfunction "GND_17") (pintype "power_in"))
      (node (ref "U2") (pin "20") (pinfunction "GND_20") (pintype "power_in"))
      (node (ref "U2") (pin "24") (pinfunction "GND_24") (pintype "power_in"))
      (node (ref "U2") (pin "26") (pinfunction "TEST_26") (pintype "input"))
      (node (ref "U2") (pin "4") (pinfunction "GND_4") (pintype "power_in"))
      (node (ref "U3") (pin "5") (pinfunction "GND_5") (pintype "bidirectional"))
      (node (ref "U3") (pin "6") (pinfunction "GND_6") (pintype "bidirectional"))
      (node (ref "U3") (pin "7") (pinfunction "GND_7") (pintype "bidirectional"))
      (node (ref "U3") (pin "8") (pinfunction "GND_8") (pintype "bidirectional"))
      (node (ref "U4") (pin "4") (pinfunction "GND_4") (pintype "power_in"))
      (node (ref "U5") (pin "2") (pinfunction "GND_2") (pintype "bidirectional"))
      (node (ref "U6") (pin "6") (pinfunction "VSS_6") (pintype "power_in"))
      (node (ref "U6") (pin "GND") (pinfunction "GND_GND") (pintype "power_in"))
      (node (ref "U7") (pin "AD2") (pinfunction "VBUS_AD2") (pintype "bidirectional"))
      (node (ref "U7") (pin "B7") (pinfunction "VSS_B7") (pintype "bidirectional"))
      (node (ref "U7") (pin "F23") (pinfunction "VSS_PA_F23") (pintype "bidirectional"))
      (node (ref "U7") (pin "GND") (pinfunction "VSS_GND") (pintype "bidirectional"))
      (node (ref "U8") (pin "4") (pinfunction "GND_4") (pintype "bidirectional"))
      (node (ref "U9") (pin "GND") (pinfunction "GND_GND") (pintype "power_in"))
      (node (ref "X2") (pin "2") (pinfunction "GND_2") (pintype "bidirectional"))
      (node (ref "X2") (pin "4") (pinfunction "GND_4") (pintype "bidirectional"))
      (node (ref "X3") (pin "2") (pinfunction "GND_2") (pintype "bidirectional"))
      (node (ref "X3") (pin "4") (pinfunction "GND_4") (pintype "bidirectional"))
      (node (ref "X4") (pin "2") (pinfunction "GND_2") (pintype "bidirectional"))
      (node (ref "X4") (pin "4") (pinfunction "GND_4") (pintype "bidirectional"))
    )
    (net (code "20") (name "GPIO0") (class "Default")
      (node (ref "GPIO0") (pin "P$1") (pinfunction "TESTPOINT_P$1") (pintype "bidirectional"))
      (node (ref "U10") (pin "42") (pinfunction "PB6_42") (pintype "bidirectional"))
    )
    (net (code "21") (name "GPIO1") (class "Default")
      (node (ref "GPIO1") (pin "P$1") (pinfunction "TESTPOINT_P$1") (pintype "bidirectional"))
      (node (ref "U10") (pin "43") (pinfunction "PB7_43") (pintype "bidirectional"))
    )
    (net (code "22") (name "GPIO2") (class "Default")
      (node (ref "TP5") (pin "P$1") (pinfunction "TESTPOINT_P$1") (pintype "bidirectional"))
      (node (ref "U10") (pin "29") (pinfunction "PA8_29") (pintype "bidirectional"))
    )
    (net (code "23") (name "GPIO3") (class "Default")
      (node (ref "TP6") (pin "P$1") (pinfunction "TESTPOINT_P$1") (pintype "bidirectional"))
      (node (ref "U10") (pin "28") (pinfunction "PB15_28") (pintype "bidirectional"))
    )
    (net (code "24") (name "LED_BLUE") (class "Default")
      (node (ref "R10") (pin "2") (pinfunction "2_2") (pintype "passive"))
      (node (ref "U10") (pin "40") (pinfunction "PB4_40") (pintype "bidirectional"))
    )
    (net (code "25") (name "LED_GREEN") (class "Default")
      (node (ref "R9") (pin "2") (pinfunction "2_2") (pintype "passive"))
      (node (ref "U10") (pin "41") (pinfunction "PB5_41") (pintype "bidirectional"))
    )
    (net (code "26") (name "LED_NRF_BLUE") (class "Default")
      (node (ref "R6") (pin "2") (pinfunction "2_2") (pintype "passive"))
      (node (ref "U7") (pin "J1") (pinfunction "P0.04/AIN2_J1") (pintype "bidirectional"))
    )
    (net (code "27") (name "LED_NRF_GREEN") (class "Default")
      (node (ref "R5") (pin "2") (pinfunction "2_2") (pintype "passive"))
      (node (ref "U7") (pin "L1") (pinfunction "P0.06_L1") (pintype "bidirectional"))
    )
    (net (code "28") (name "LED_NRF_RED") (class "Default")
      (node (ref "R4") (pin "2") (pinfunction "2_2") (pintype "passive"))
      (node (ref "U7") (pin "K2") (pinfunction "P0.05/AIN3_K2") (pintype "bidirectional"))
    )
    (net (code "29") (name "LED_RED") (class "Default")
      (node (ref "R8") (pin "2") (pinfunction "2_2") (pintype "passive"))
      (node (ref "U10") (pin "39") (pinfunction "PB3_39") (pintype "bidirectional"))
    )
    (net (code "30") (name "NRF_GPIO_0") (class "Default")
      (node (ref "TP13") (pin "P$1") (pinfunction "TESTPOINT_P$1") (pintype "bidirectional"))
      (node (ref "U7") (pin "H2") (pinfunction "P0.27_H2") (pintype "bidirectional"))
    )
    (net (code "31") (name "NRF_GPIO_1") (class "Default")
      (node (ref "TP14") (pin "P$1") (pinfunction "TESTPOINT_P$1") (pintype "bidirectional"))
      (node (ref "U7") (pin "G1") (pinfunction "P0.26_G1") (pintype "bidirectional"))
    )
    (net (code "32") (name "NRF_IMU_INT1") (class "Default")
      (node (ref "U3") (pin "12") (pinfunction "INT1_12") (pintype "bidirectional"))
      (node (ref "U7") (pin "AD18") (pinfunction "P0.22_AD18") (pintype "bidirectional"))
    )
    (net (code "33") (name "NRF_IMU_INT2") (class "Default")
      (node (ref "U3") (pin "11") (pinfunction "INT2_11") (pintype "bidirectional"))
      (node (ref "U7") (pin "AD20") (pinfunction "P0.24_AD20") (pintype "bidirectional"))
    )
    (net (code "34") (name "NRF_MISO") (class "Default")
      (node (ref "J2") (pin "7") (pinfunction "DATA0/MISO_7") (pintype "bidirectional"))
      (node (ref "R14") (pin "1") (pinfunction "1_1") (pintype "passive"))
      (node (ref "U3") (pin "3") (pinfunction "MISO/SA0_3") (pintype "bidirectional"))
      (node (ref "U7") (pin "AD10") (pinfunction "P0.15_AD10") (pintype "bidirectional"))
    )
    (net (code "35") (name "NRF_MOSI") (class "Default")
      (node (ref "J2") (pin "3") (pinfunction "CMD/MOSI_3") (pintype "bidirectional"))
      (node (ref "R12") (pin "1") (pinfunction "1_1") (pintype "passive"))
      (node (ref "U3") (pin "4") (pinfunction "MOSI/SDA_4") (pintype "bidirectional"))
      (node (ref "U7") (pin "AD8") (pinfunction "P0.13_AD8") (pintype "bidirectional"))
    )
    (net (code "36") (name "NRF_SCK") (class "Default")
      (node (ref "J2") (pin "5") (pinfunction "CLK_5") (pintype "bidirectional"))
      (node (ref "U3") (pin "1") (pinfunction "SCL/SPC_1") (pintype "bidirectional"))
      (node (ref "U7") (pin "AD12") (pinfunction "P0.17_AD12") (pintype "bidirectional"))
    )
    (net (code "37") (name "NRF_SWDCLK") (class "Default")
      (node (ref "J4") (pin "4") (pinfunction "SWDCLK_4") (pintype "bidirectional"))
      (node (ref "U7") (pin "AA24") (pinfunction "SWDCLK_AA24") (pintype "bidirectional"))
    )
    (net (code "38") (name "NRF_SWDIO") (class "Default")
      (node (ref "J4") (pin "2") (pinfunction "SWDIO_2") (pintype "bidirectional"))
      (node (ref "U7") (pin "AC24") (pinfunction "SWDIO_AC24") (pintype "bidirectional"))
    )
    (net (code "39") (name "Net-(A4-ANTENNA)") (class "Default")
      (node (ref "A4") (pin "S1") (pinfunction "ANTENNA_S1") (pintype "bidirectional"))
      (node (ref "C2") (pin "1") (pinfunction "1_1") (pintype "bidirectional"))
      (node (ref "L1") (pin "1") (pinfunction "1_1") (pintype "bidirectional"))
    )
    (net (code "40") (name "Net-(C6-2)") (class "Default")
      (node (ref "C6") (pin "P$2") (pinfunction "2_P$2") (pintype "bidirectional"))
      (node (ref "T1") (pin "3") (pinfunction "BAL/3_3") (pintype "bidirectional"))
    )
    (net (code "41") (name "Net-(C7-2)") (class "Default")
      (node (ref "C7") (pin "P$2") (pinfunction "2_P$2") (pintype "bidirectional"))
      (node (ref "T1") (pin "4") (pinfunction "BAL/4_4") (pintype "bidirectional"))
    )
    (net (code "42") (name "Net-(C17-Pad1)") (class "Default")
      (node (ref "C17") (pin "1") (pinfunction "1_1") (pintype "bidirectional"))
      (node (ref "R17") (pin "2") (pinfunction "2_2") (pintype "passive"))
    )
    (net (code "43") (name "Net-(C22-Pad1)") (class "Default")
      (node (ref "C22") (pin "1") (pinfunction "1_1") (pintype "bidirectional"))
      (node (ref "R3") (pin "2") (pinfunction "2_2") (pintype "passive"))
    )
    (net (code "44") (name "Net-(D1-PadA)") (class "Default")
      (node (ref "D1") (pin "A") (pinfunction "A_A") (pintype "passive"))
      (node (ref "R7") (pin "1") (pinfunction "1_1") (pintype "passive"))
    )
    (net (code "45") (name "Net-(D2-B)") (class "Default")
      (node (ref "D2") (pin "3") (pinfunction "B_3") (pintype "output"))
      (node (ref "R6") (pin "1") (pinfunction "1_1") (pintype "passive"))
    )
    (net (code "46") (name "Net-(D2-G)") (class "Default")
      (node (ref "D2") (pin "4") (pinfunction "G_4") (pintype "output"))
      (node (ref "R5") (pin "1") (pinfunction "1_1") (pintype "passive"))
    )
    (net (code "47") (name "Net-(D2-R)") (class "Default")
      (node (ref "D2") (pin "2") (pinfunction "R_2") (pintype "output"))
      (node (ref "R4") (pin "1") (pinfunction "1_1") (pintype "passive"))
    )
    (net (code "48") (name "Net-(D3-B)") (class "Default")
      (node (ref "D3") (pin "3") (pinfunction "B_3") (pintype "output"))
      (node (ref "R10") (pin "1") (pinfunction "1_1") (pintype "passive"))
      (node (ref "TP9") (pin "P$1") (pinfunction "TESTPOINT_P$1") (pintype "bidirectional"))
    )
    (net (code "49") (name "Net-(D3-G)") (class "Default")
      (node (ref "D3") (pin "4") (pinfunction "G_4") (pintype "output"))
      (node (ref "R9") (pin "1") (pinfunction "1_1") (pintype "passive"))
      (node (ref "TP7") (pin "P$1") (pinfunction "TESTPOINT_P$1") (pintype "bidirectional"))
    )
    (net (code "50") (name "Net-(D3-R)") (class "Default")
      (node (ref "D3") (pin "2") (pinfunction "R_2") (pintype "output"))
      (node (ref "R8") (pin "1") (pinfunction "1_1") (pintype "passive"))
      (node (ref "TP8") (pin "P$1") (pinfunction "TESTPOINT_P$1") (pintype "bidirectional"))
    )
    (net (code "51") (name "Net-(J2-VCC)") (class "Default")
      (node (ref "C60") (pin "1") (pinfunction "1_1") (pintype "bidirectional"))
      (node (ref "J2") (pin "4") (pinfunction "VCC_4") (pintype "bidirectional"))
      (node (ref "R12") (pin "2") (pinfunction "2_2") (pintype "passive"))
      (node (ref "R13") (pin "2") (pinfunction "2_2") (pintype "passive"))
      (node (ref "R14") (pin "2") (pinfunction "2_2") (pintype "passive"))
      (node (ref "R19") (pin "2") (pinfunction "2_2") (pintype "passive"))
      (node (ref "U8") (pin "1") (pinfunction "VLOAD_1") (pintype "bidirectional"))
      (node (ref "U8") (pin "2") (pinfunction "VLOAD_2") (pintype "bidirectional"))
    )
    (net (code "52") (name "Net-(L2-Pad2)") (class "Default")
      (node (ref "L2") (pin "2") (pinfunction "2_2") (pintype "bidirectional"))
      (node (ref "L6") (pin "1") (pinfunction "1_1") (pintype "bidirectional"))
    )
    (net (code "53") (name "Net-(T1-UNB)") (class "Default")
      (node (ref "T1") (pin "1") (pinfunction "UNB_1") (pintype "bidirectional"))
      (node (ref "U9") (pin "1") (pinfunction "RFC_1") (pintype "bidirectional"))
    )
    (net (code "54") (name "Net-(TP11-TESTPOINT)") (class "Default")
      (node (ref "TP11") (pin "P$1") (pinfunction "TESTPOINT_P$1") (pintype "bidirectional"))
      (node (ref "U1") (pin "36") (pinfunction "GPIO2_36") (pintype "bidirectional"))
    )
    (net (code "55") (name "Net-(TP12-TESTPOINT)") (class "Default")
      (node (ref "TP12") (pin "P$1") (pinfunction "TESTPOINT_P$1") (pintype "bidirectional"))
      (node (ref "U1") (pin "35") (pinfunction "GPIO3_35") (pintype "bidirectional"))
    )
    (net (code "56") (name "Net-(U1-CLKTUNE)") (class "Default")
      (node (ref "C3") (pin "1") (pinfunction "1_1") (pintype "bidirectional"))
      (node (ref "R17") (pin "1") (pinfunction "1_1") (pintype "passive"))
      (node (ref "U1") (pin "8") (pinfunction "CLKTUNE_8") (pintype "bidirectional"))
    )
    (net (code "57") (name "Net-(U1-VCOTUNE)") (class "Default")
      (node (ref "C16") (pin "1") (pinfunction "1_1") (pintype "bidirectional"))
      (node (ref "R3") (pin "1") (pinfunction "1_1") (pintype "passive"))
      (node (ref "U1") (pin "12") (pinfunction "VCOTUNE_12") (pintype "bidirectional"))
    )
    (net (code "58") (name "Net-(U1-VREF)") (class "Default")
      (node (ref "R15") (pin "2") (pinfunction "2_2") (pintype "passive"))
      (node (ref "U1") (pin "5") (pinfunction "VREF_5") (pintype "bidirectional"))
    )
    (net (code "59") (name "Net-(U2-3V3OUT)") (class "Default")
      (node (ref "C28") (pin "1") (pinfunction "1_1") (pintype "bidirectional"))
      (node (ref "U2") (pin "1") (pinfunction "VCCIO_1") (pintype "power_in"))
      (node (ref "U2") (pin "16") (pinfunction "3V3OUT_16") (pintype "output"))
    )
    (net (code "60") (name "Net-(U2-RXD)") (class "Default")
      (node (ref "R2") (pin "1") (pinfunction "1_1") (pintype "passive"))
      (node (ref "U2") (pin "2") (pinfunction "RXD_2") (pintype "input"))
    )
    (net (code "61") (name "Net-(U2-TXD)") (class "Default")
      (node (ref "R1") (pin "1") (pinfunction "1_1") (pintype "passive"))
      (node (ref "U2") (pin "30") (pinfunction "TXD_30") (pintype "output"))
    )
    (net (code "62") (name "Net-(U5-BP)") (class "Default")
      (node (ref "C23") (pin "1") (pinfunction "1_1") (pintype "bidirectional"))
      (node (ref "U5") (pin "4") (pinfunction "BP_4") (pintype "bidirectional"))
    )
    (net (code "63") (name "Net-(U6-PROG)") (class "Default")
      (node (ref "R11") (pin "2") (pinfunction "2_2") (pintype "passive"))
      (node (ref "U6") (pin "8") (pinfunction "PROG_8") (pintype "bidirectional"))
    )
    (net (code "64") (name "Net-(U6-STAT)") (class "Default")
      (node (ref "D1") (pin "C") (pinfunction "C_C") (pintype "passive"))
      (node (ref "U6") (pin "5") (pinfunction "STAT_5") (pintype "bidirectional"))
    )
    (net (code "65") (name "Net-(U7-ANT)") (class "Default")
      (node (ref "C1") (pin "1") (pinfunction "1_1") (pintype "bidirectional"))
      (node (ref "L1") (pin "2") (pinfunction "2_2") (pintype "bidirectional"))
      (node (ref "U7") (pin "H23") (pinfunction "ANT_H23") (pintype "bidirectional"))
    )
    (net (code "66") (name "Net-(U7-DCC)") (class "Default")
      (node (ref "L6") (pin "2") (pinfunction "2_2") (pintype "bidirectional"))
      (node (ref "U7") (pin "B3") (pinfunction "DCC_B3") (pintype "bidirectional"))
    )
    (net (code "67") (name "Net-(U7-DEC1)") (class "Default")
      (node (ref "C32") (pin "1") (pinfunction "1_1") (pintype "bidirectional"))
      (node (ref "U7") (pin "C1") (pinfunction "DEC1_C1") (pintype "bidirectional"))
    )
    (net (code "68") (name "Net-(U7-DEC3)") (class "Default")
      (node (ref "C18") (pin "1") (pinfunction "1_1") (pintype "bidirectional"))
      (node (ref "U7") (pin "D23") (pinfunction "DEC3_D23") (pintype "bidirectional"))
    )
    (net (code "69") (name "Net-(U7-DEC4)") (class "Default")
      (node (ref "C26") (pin "1") (pinfunction "1_1") (pintype "bidirectional"))
      (node (ref "C56") (pin "1") (pinfunction "1_1") (pintype "bidirectional"))
      (node (ref "L2") (pin "1") (pinfunction "1_1") (pintype "bidirectional"))
      (node (ref "U7") (pin "B5") (pinfunction "DEC4_B5") (pintype "bidirectional"))
      (node (ref "U7") (pin "E24") (pinfunction "DEC6_E24") (pintype "bidirectional"))
    )
    (net (code "70") (name "Net-(U7-DEC5)") (class "Default")
      (node (ref "C21") (pin "1") (pinfunction "1_1") (pintype "bidirectional"))
      (node (ref "U7") (pin "N24") (pinfunction "DEC5_N24") (pintype "bidirectional"))
    )
    (net (code "71") (name "Net-(U7-XC1)") (class "Default")
      (node (ref "C8") (pin "2") (pinfunction "2_2") (pintype "bidirectional"))
      (node (ref "U7") (pin "B24") (pinfunction "XC1_B24") (pintype "bidirectional"))
      (node (ref "X3") (pin "3") (pinfunction "2_3") (pintype "bidirectional"))
    )
    (net (code "72") (name "Net-(U7-XC2)") (class "Default")
      (node (ref "C9") (pin "2") (pinfunction "2_2") (pintype "bidirectional"))
      (node (ref "U7") (pin "A23") (pinfunction "XC2_A23") (pintype "bidirectional"))
      (node (ref "X3") (pin "1") (pinfunction "1_1") (pintype "bidirectional"))
    )
    (net (code "73") (name "Net-(U10-PF11-BOOT0)") (class "Default")
      (node (ref "R16") (pin "1") (pinfunction "1_1") (pintype "passive"))
      (node (ref "U10") (pin "44") (pinfunction "PF11-BOOT0_44") (pintype "bidirectional"))
    )
    (net (code "74") (name "OSC_IN") (class "Default")
      (node (ref "C14") (pin "1") (pinfunction "1_1") (pintype "bidirectional"))
      (node (ref "U10") (pin "5") (pinfunction "PF0-OSC_IN_5") (pintype "bidirectional"))
      (node (ref "X2") (pin "1") (pinfunction "1_1") (pintype "bidirectional"))
    )
    (net (code "75") (name "OSC_OUT") (class "Default")
      (node (ref "C15") (pin "1") (pinfunction "1_1") (pintype "bidirectional"))
      (node (ref "U10") (pin "6") (pinfunction "PF1-OSC_OUT_6") (pintype "bidirectional"))
      (node (ref "X2") (pin "3") (pinfunction "2_3") (pintype "bidirectional"))
    )
    (net (code "76") (name "REG_EN") (class "Default")
      (node (ref "U1") (pin "21") (pinfunction "EXTON_21") (pintype "output"))
      (node (ref "U4") (pin "2") (pinfunction "EN_2") (pintype "bidirectional"))
    )
    (net (code "77") (name "RF1") (class "Default")
      (node (ref "A1") (pin "A") (pinfunction "ANTENNA_A") (pintype "bidirectional"))
      (node (ref "U9") (pin "4") (pinfunction "RF1_4") (pintype "bidirectional"))
    )
    (net (code "78") (name "RF2") (class "Default")
      (node (ref "A2") (pin "A") (pinfunction "ANTENNA_A") (pintype "bidirectional"))
      (node (ref "U9") (pin "5") (pinfunction "RF2_5") (pintype "bidirectional"))
    )
    (net (code "79") (name "RF3") (class "Default")
      (node (ref "A3") (pin "A") (pinfunction "ANTENNA_A") (pintype "bidirectional"))
      (node (ref "U9") (pin "8") (pinfunction "RF3_8") (pintype "bidirectional"))
    )
    (net (code "80") (name "RF_N") (class "Default")
      (node (ref "C6") (pin "P$1") (pinfunction "1_P$1") (pintype "bidirectional"))
      (node (ref "U1") (pin "17") (pinfunction "RF_N_17") (pintype "bidirectional"))
    )
    (net (code "81") (name "RF_P") (class "Default")
      (node (ref "C7") (pin "P$1") (pinfunction "1_P$1") (pintype "bidirectional"))
      (node (ref "U1") (pin "16") (pinfunction "RF_P_16") (pintype "bidirectional"))
    )
    (net (code "82") (name "SD_EN") (class "Default")
      (node (ref "R18") (pin "1") (pinfunction "1_1") (pintype "passive"))
      (node (ref "U7") (pin "AC9") (pinfunction "P0.14_AC9") (pintype "bidirectional"))
      (node (ref "U8") (pin "3") (pinfunction "EN_3") (pintype "bidirectional"))
    )
    (net (code "83") (name "STM_INTERRUPT") (class "Default")
      (node (ref "TP3") (pin "TP") (pinfunction "TP_TP") (pintype "input"))
      (node (ref "U10") (pin "12") (pinfunction "PA2_12") (pintype "bidirectional"))
      (node (ref "U7") (pin "N1") (pinfunction "P0.08_N1") (pintype "bidirectional"))
    )
    (net (code "84") (name "STM_SWCLK") (class "Default")
      (node (ref "J5") (pin "4") (pinfunction "SWDCLK_4") (pintype "bidirectional"))
      (node (ref "U10") (pin "37") (pinfunction "PA14_37") (pintype "bidirectional"))
    )
    (net (code "85") (name "STM_SWDIO") (class "Default")
      (node (ref "J5") (pin "2") (pinfunction "SWDIO_2") (pintype "bidirectional"))
      (node (ref "U10") (pin "34") (pinfunction "PA13_34") (pintype "bidirectional"))
    )
    (net (code "86") (name "VBAT") (class "Default")
      (node (ref "C58") (pin "1") (pinfunction "1_1") (pintype "bidirectional"))
      (node (ref "C68") (pin "1") (pinfunction "1_1") (pintype "bidirectional"))
      (node (ref "J1") (pin "P") (pinfunction "+_P") (pintype "bidirectional"))
      (node (ref "R22") (pin "2") (pinfunction "2_2") (pintype "passive"))
      (node (ref "U5") (pin "1") (pinfunction "IN_1") (pintype "bidirectional"))
      (node (ref "U5") (pin "3") (pinfunction "~{SHDN}_3") (pintype "bidirectional"))
      (node (ref "U6") (pin "3") (pinfunction "VBAT/3_3") (pintype "power_in"))
      (node (ref "U6") (pin "4") (pinfunction "VBAT/4_4") (pintype "power_in"))
      (node (ref "U7") (pin "B9") (pinfunction "P0.30/AIN6_B9") (pintype "bidirectional"))
    )
    (net (code "87") (name "VDDCLK") (class "Default")
      (node (ref "C39") (pin "1") (pinfunction "1_1") (pintype "bidirectional"))
      (node (ref "U1") (pin "9") (pinfunction "VDDCLK_9") (pintype "power_in"))
    )
    (net (code "88") (name "VDDDIG") (class "Default")
      (node (ref "C35") (pin "1") (pinfunction "1_1") (pintype "bidirectional"))
      (node (ref "C36") (pin "1") (pinfunction "1_1") (pintype "bidirectional"))
      (node (ref "U1") (pin "20") (pinfunction "VDDREG_20") (pintype "power_in"))
      (node (ref "U1") (pin "44") (pinfunction "VDDDIG_44") (pintype "power_in"))
    )
    (net (code "89") (name "VDDIF") (class "Default")
      (node (ref "C42") (pin "1") (pinfunction "1_1") (pintype "bidirectional"))
      (node (ref "U1") (pin "7") (pinfunction "VDDIF_7") (pintype "power_in"))
    )
    (net (code "90") (name "VDDIO") (class "Default")
      (node (ref "C41") (pin "1") (pinfunction "1_1") (pintype "bidirectional"))
      (node (ref "C53") (pin "1") (pinfunction "1_1") (pintype "bidirectional"))
      (node (ref "U1") (pin "31") (pinfunction "VDDIO/31_31") (pintype "power_in"))
      (node (ref "U1") (pin "42") (pinfunction "VDDIO/42_42") (pintype "power_in"))
    )
    (net (code "91") (name "VDDMS") (class "Default")
      (node (ref "C38") (pin "1") (pinfunction "1_1") (pintype "bidirectional"))
      (node (ref "U1") (pin "6") (pinfunction "VDDMS_6") (pintype "power_in"))
    )
    (net (code "92") (name "VDDSYN") (class "Default")
      (node (ref "C40") (pin "1") (pinfunction "1_1") (pintype "bidirectional"))
      (node (ref "U1") (pin "10") (pinfunction "VDDSYN_10") (pintype "power_in"))
    )
    (net (code "93") (name "VDDVCO") (class "Default")
      (node (ref "C43") (pin "1") (pinfunction "1_1") (pintype "bidirectional"))
      (node (ref "U1") (pin "11") (pinfunction "VDDVCO_11") (pintype "power_in"))
    )
    (net (code "94") (name "VUSB") (class "Default")
      (node (ref "C54") (pin "1") (pinfunction "1_1") (pintype "bidirectional"))
      (node (ref "C67") (pin "1") (pinfunction "1_1") (pintype "bidirectional"))
      (node (ref "J3") (pin "1") (pinfunction "+5V_1") (pintype "bidirectional"))
      (node (ref "R7") (pin "2") (pinfunction "2_2") (pintype "passive"))
      (node (ref "U2") (pin "19") (pinfunction "VCC_19") (pintype "power_in"))
      (node (ref "U6") (pin "1") (pinfunction "VDD/1_1") (pintype "power_in"))
      (node (ref "U6") (pin "2") (pinfunction "VDD/2_2") (pintype "power_in"))
    )
    (net (code "95") (name "XL3") (class "Default")
      (node (ref "C11") (pin "2") (pinfunction "2_2") (pintype "bidirectional"))
      (node (ref "U7") (pin "D2") (pinfunction "P0.00/XL1_D2") (pintype "bidirectional"))
      (node (ref "X1") (pin "A") (pinfunction "1_A") (pintype "bidirectional"))
    )
    (net (code "96") (name "XL4") (class "Default")
      (node (ref "C10") (pin "2") (pinfunction "2_2") (pintype "bidirectional"))
      (node (ref "U7") (pin "F2") (pinfunction "P0.01/XL2_F2") (pintype "bidirectional"))
      (node (ref "X1") (pin "B") (pinfunction "2_B") (pintype "bidirectional"))
    )
    (net (code "97") (name "XTAL1") (class "Default")
      (node (ref "C13") (pin "1") (pinfunction "1_1") (pintype "bidirectional"))
      (node (ref "U1") (pin "3") (pinfunction "XTAL1_3") (pintype "input"))
      (node (ref "X4") (pin "3") (pinfunction "2_3") (pintype "bidirectional"))
    )
    (net (code "98") (name "XTAL2") (class "Default")
      (node (ref "C12") (pin "1") (pinfunction "1_1") (pintype "bidirectional"))
      (node (ref "U1") (pin "4") (pinfunction "XTAL2_4") (pintype "input"))
      (node (ref "X4") (pin "1") (pinfunction "1_1") (pintype "bidirectional"))
    )
    (net (code "99") (name "unconnected-(J2-DATA1{slash}RSV-Pad8)") (class "Default")
      (node (ref "J2") (pin "8") (pinfunction "DATA1/RSV_8") (pintype "bidirectional"))
    )
    (net (code "100") (name "unconnected-(J2-DATA2{slash}NC-Pad1)") (class "Default")
      (node (ref "J2") (pin "1") (pinfunction "DATA2/NC_1") (pintype "bidirectional"))
    )
    (net (code "101") (name "unconnected-(J3-ID-Pad4)") (class "Default")
      (node (ref "J3") (pin "4") (pinfunction "ID_4") (pintype "bidirectional"))
    )
    (net (code "102") (name "unconnected-(J4-SWO-Pad6)") (class "Default")
      (node (ref "J4") (pin "6") (pinfunction "SWO_6") (pintype "bidirectional"))
    )
    (net (code "103") (name "unconnected-(J4-~{RESET}-Pad3)") (class "Default")
      (node (ref "J4") (pin "3") (pinfunction "~{RESET}_3") (pintype "bidirectional"))
    )
    (net (code "104") (name "unconnected-(J5-SWO-Pad6)") (class "Default")
      (node (ref "J5") (pin "6") (pinfunction "SWO_6") (pintype "bidirectional"))
    )
    (net (code "105") (name "unconnected-(U1-GPIO0-Pad38)") (class "Default")
      (node (ref "U1") (pin "38") (pinfunction "GPIO0_38") (pintype "bidirectional"))
    )
    (net (code "106") (name "unconnected-(U1-GPIO1-Pad37)") (class "Default")
      (node (ref "U1") (pin "37") (pinfunction "GPIO1_37") (pintype "bidirectional"))
    )
    (net (code "107") (name "unconnected-(U1-GPIO4-Pad34)") (class "Default")
      (node (ref "U1") (pin "34") (pinfunction "GPIO4_34") (pintype "bidirectional"))
    )
    (net (code "108") (name "unconnected-(U1-GPIO5-Pad33)") (class "Default")
      (node (ref "U1") (pin "33") (pinfunction "GPIO5_33") (pintype "bidirectional"))
    )
    (net (code "109") (name "unconnected-(U1-GPIO6-Pad30)") (class "Default")
      (node (ref "U1") (pin "30") (pinfunction "GPIO6_30") (pintype "bidirectional"))
    )
    (net (code "110") (name "unconnected-(U2-CBUS0-Pad22)") (class "Default")
      (node (ref "U2") (pin "22") (pinfunction "CBUS0_22") (pintype "bidirectional"))
    )
    (net (code "111") (name "unconnected-(U2-CBUS1-Pad21)") (class "Default")
      (node (ref "U2") (pin "21") (pinfunction "CBUS1_21") (pintype "bidirectional"))
    )
    (net (code "112") (name "unconnected-(U2-CBUS2-Pad10)") (class "Default")
      (node (ref "U2") (pin "10") (pinfunction "CBUS2_10") (pintype "bidirectional"))
    )
    (net (code "113") (name "unconnected-(U2-CBUS3-Pad11)") (class "Default")
      (node (ref "U2") (pin "11") (pinfunction "CBUS3_11") (pintype "bidirectional"))
    )
    (net (code "114") (name "unconnected-(U2-CBUS4-Pad9)") (class "Default")
      (node (ref "U2") (pin "9") (pinfunction "CBUS4_9") (pintype "bidirectional"))
    )
    (net (code "115") (name "unconnected-(U2-OSCI-Pad27)") (class "Default")
      (node (ref "U2") (pin "27") (pinfunction "OSCI_27") (pintype "input"))
    )
    (net (code "116") (name "unconnected-(U2-OSCO-Pad28)") (class "Default")
      (node (ref "U2") (pin "28") (pinfunction "OSCO_28") (pintype "output"))
    )
    (net (code "117") (name "unconnected-(U2-~{CTS}-Pad8)") (class "Default")
      (node (ref "U2") (pin "8") (pinfunction "~{CTS}_8") (pintype "input"))
    )
    (net (code "118") (name "unconnected-(U2-~{DCD}-Pad7)") (class "Default")
      (node (ref "U2") (pin "7") (pinfunction "~{DCD}_7") (pintype "input"))
    )
    (net (code "119") (name "unconnected-(U2-~{DSR}-Pad6)") (class "Default")
      (node (ref "U2") (pin "6") (pinfunction "~{DSR}_6") (pintype "input"))
    )
    (net (code "120") (name "unconnected-(U2-~{DTR}-Pad31)") (class "Default")
      (node (ref "U2") (pin "31") (pinfunction "~{DTR}_31") (pintype "output"))
    )
    (net (code "121") (name "unconnected-(U2-~{RI}-Pad3)") (class "Default")
      (node (ref "U2") (pin "3") (pinfunction "~{RI}_3") (pintype "input"))
    )
    (net (code "122") (name "unconnected-(U2-~{RTS}-Pad32)") (class "Default")
      (node (ref "U2") (pin "32") (pinfunction "~{RTS}_32") (pintype "output"))
    )
    (net (code "123") (name "unconnected-(U6-NC-Pad7)") (class "Default")
      (node (ref "U6") (pin "7") (pinfunction "NC_7") (pintype "no_connect"))
    )
    (net (code "124") (name "unconnected-(U7-D+-PadAD6)") (class "Default")
      (node (ref "U7") (pin "AD6") (pinfunction "D+_AD6") (pintype "bidirectional"))
    )
    (net (code "125") (name "unconnected-(U7-D--PadAD4)") (class "Default")
      (node (ref "U7") (pin "AD4") (pinfunction "D-_AD4") (pintype "bidirectional"))
    )
    (net (code "126") (name "unconnected-(U7-DCCH-PadAB2)") (class "Default")
      (node (ref "U7") (pin "AB2") (pinfunction "DCCH_AB2") (pintype "bidirectional"))
    )
    (net (code "127") (name "unconnected-(U7-DEC2-PadA18)") (class "Default")
      (node (ref "U7") (pin "A18") (pinfunction "DEC2_A18") (pintype "bidirectional"))
    )
    (net (code "128") (name "unconnected-(U7-DECUSB-PadAC5)") (class "Default")
      (node (ref "U7") (pin "AC5") (pinfunction "DECUSB_AC5") (pintype "bidirectional"))
    )
    (net (code "129") (name "unconnected-(U7-P0.02{slash}AIN0-PadA12)") (class "Default")
      (node (ref "U7") (pin "A12") (pinfunction "P0.02/AIN0_A12") (pintype "bidirectional"))
    )
    (net (code "130") (name "unconnected-(U7-P0.03{slash}AIN1-PadB13)") (class "Default")
      (node (ref "U7") (pin "B13") (pinfunction "P0.03/AIN1_B13") (pintype "bidirectional"))
    )
    (net (code "131") (name "unconnected-(U7-P0.09{slash}NFC1-PadL24)") (class "Default")
      (node (ref "U7") (pin "L24") (pinfunction "P0.09/NFC1_L24") (pintype "bidirectional"))
    )
    (net (code "132") (name "unconnected-(U7-P0.10{slash}NFC2-PadJ24)") (class "Default")
      (node (ref "U7") (pin "J24") (pinfunction "P0.10/NFC2_J24") (pintype "bidirectional"))
    )
    (net (code "133") (name "unconnected-(U7-P0.19-PadAC15)") (class "Default")
      (node (ref "U7") (pin "AC15") (pinfunction "P0.19_AC15") (pintype "bidirectional"))
    )
    (net (code "134") (name "unconnected-(U7-P0.20-PadAD16)") (class "Default")
      (node (ref "U7") (pin "AD16") (pinfunction "P0.20_AD16") (pintype "bidirectional"))
    )
    (net (code "135") (name "unconnected-(U7-P0.21-PadAC17)") (class "Default")
      (node (ref "U7") (pin "AC17") (pinfunction "P0.21_AC17") (pintype "bidirectional"))
    )
    (net (code "136") (name "unconnected-(U7-P0.23-PadAC19)") (class "Default")
      (node (ref "U7") (pin "AC19") (pinfunction "P0.23_AC19") (pintype "bidirectional"))
    )
    (net (code "137") (name "unconnected-(U7-P0.25-PadAC21)") (class "Default")
      (node (ref "U7") (pin "AC21") (pinfunction "P0.25_AC21") (pintype "bidirectional"))
    )
    (net (code "138") (name "unconnected-(U7-P0.28{slash}AIN4-PadB11)") (class "Default")
      (node (ref "U7") (pin "B11") (pinfunction "P0.28/AIN4_B11") (pintype "bidirectional"))
    )
    (net (code "139") (name "unconnected-(U7-P0.29{slash}AIN5-PadA10)") (class "Default")
      (node (ref "U7") (pin "A10") (pinfunction "P0.29/AIN5_A10") (pintype "bidirectional"))
    )
    (net (code "140") (name "unconnected-(U7-P0.31{slash}AIN7-PadA8)") (class "Default")
      (node (ref "U7") (pin "A8") (pinfunction "P0.31/AIN7_A8") (pintype "bidirectional"))
    )
    (net (code "141") (name "unconnected-(U7-P1.01-PadY23)") (class "Default")
      (node (ref "U7") (pin "Y23") (pinfunction "P1.01_Y23") (pintype "bidirectional"))
    )
    (net (code "142") (name "unconnected-(U7-P1.02-PadW24)") (class "Default")
      (node (ref "U7") (pin "W24") (pinfunction "P1.02_W24") (pintype "bidirectional"))
    )
    (net (code "143") (name "unconnected-(U7-P1.03-PadV23)") (class "Default")
      (node (ref "U7") (pin "V23") (pinfunction "P1.03_V23") (pintype "bidirectional"))
    )
    (net (code "144") (name "unconnected-(U7-P1.04-PadU24)") (class "Default")
      (node (ref "U7") (pin "U24") (pinfunction "P1.04_U24") (pintype "bidirectional"))
    )
    (net (code "145") (name "unconnected-(U7-P1.05-PadT23)") (class "Default")
      (node (ref "U7") (pin "T23") (pinfunction "P1.05_T23") (pintype "bidirectional"))
    )
    (net (code "146") (name "unconnected-(U7-P1.06-PadR24)") (class "Default")
      (node (ref "U7") (pin "R24") (pinfunction "P1.06_R24") (pintype "bidirectional"))
    )
    (net (code "147") (name "unconnected-(U7-P1.07-PadP23)") (class "Default")
      (node (ref "U7") (pin "P23") (pinfunction "P1.07_P23") (pintype "bidirectional"))
    )
    (net (code "148") (name "unconnected-(U7-P1.10-PadA20)") (class "Default")
      (node (ref "U7") (pin "A20") (pinfunction "P1.10_A20") (pintype "bidirectional"))
    )
    (net (code "149") (name "unconnected-(U7-P1.11-PadB19)") (class "Default")
      (node (ref "U7") (pin "B19") (pinfunction "P1.11_B19") (pintype "bidirectional"))
    )
    (net (code "150") (name "unconnected-(U7-P1.12-PadB17)") (class "Default")
      (node (ref "U7") (pin "B17") (pinfunction "P1.12_B17") (pintype "bidirectional"))
    )
    (net (code "151") (name "unconnected-(U7-P1.13-PadA16)") (class "Default")
      (node (ref "U7") (pin "A16") (pinfunction "P1.13_A16") (pintype "bidirectional"))
    )
    (net (code "152") (name "unconnected-(U7-P1.14-PadB15)") (class "Default")
      (node (ref "U7") (pin "B15") (pinfunction "P1.14_B15") (pintype "bidirectional"))
    )
    (net (code "153") (name "unconnected-(U7-P1.15-PadA14)") (class "Default")
      (node (ref "U7") (pin "A14") (pinfunction "P1.15_A14") (pintype "bidirectional"))
    )
    (net (code "154") (name "unconnected-(U10-PA0-Pad10)") (class "Default")
      (node (ref "U10") (pin "10") (pinfunction "PA0_10") (pintype "bidirectional"))
    )
    (net (code "155") (name "unconnected-(U10-PA1-Pad11)") (class "Default")
      (node (ref "U10") (pin "11") (pinfunction "PA1_11") (pintype "bidirectional"))
    )
    (net (code "156") (name "unconnected-(U10-PA3-Pad13)") (class "Default")
      (node (ref "U10") (pin "13") (pinfunction "PA3_13") (pintype "bidirectional"))
    )
    (net (code "157") (name "unconnected-(U10-PA11-Pad32)") (class "Default")
      (node (ref "U10") (pin "32") (pinfunction "PA11_32") (pintype "bidirectional"))
    )
    (net (code "158") (name "unconnected-(U10-PA12-Pad33)") (class "Default")
      (node (ref "U10") (pin "33") (pinfunction "PA12_33") (pintype "bidirectional"))
    )
    (net (code "159") (name "unconnected-(U10-PA15-Pad38)") (class "Default")
      (node (ref "U10") (pin "38") (pinfunction "PA15_38") (pintype "bidirectional"))
    )
    (net (code "160") (name "unconnected-(U10-PB8-Pad45)") (class "Default")
      (node (ref "U10") (pin "45") (pinfunction "PB8_45") (pintype "bidirectional"))
    )
    (net (code "161") (name "unconnected-(U10-PB9-Pad46)") (class "Default")
      (node (ref "U10") (pin "46") (pinfunction "PB9_46") (pintype "bidirectional"))
    )
    (net (code "162") (name "unconnected-(U10-PB10-Pad21)") (class "Default")
      (node (ref "U10") (pin "21") (pinfunction "PB10_21") (pintype "bidirectional"))
    )
    (net (code "163") (name "unconnected-(U10-PB11-Pad22)") (class "Default")
      (node (ref "U10") (pin "22") (pinfunction "PB11_22") (pintype "bidirectional"))
    )
    (net (code "164") (name "unconnected-(U10-PC13-Pad2)") (class "Default")
      (node (ref "U10") (pin "2") (pinfunction "PC13_2") (pintype "bidirectional"))
    )
    (net (code "165") (name "unconnected-(U10-PC14-OSC32_IN-Pad3)") (class "Default")
      (node (ref "U10") (pin "3") (pinfunction "PC14-OSC32_IN_3") (pintype "bidirectional"))
    )
    (net (code "166") (name "unconnected-(U10-PC15-OSC32_OUT-Pad4)") (class "Default")
      (node (ref "U10") (pin "4") (pinfunction "PC15-OSC32_OUT_4") (pintype "bidirectional"))
    )
    (net (code "167") (name "~{DW_RST}") (class "Default")
      (node (ref "U1") (pin "27") (pinfunction "~{RST}_27") (pintype "bidirectional"))
      (node (ref "U10") (pin "18") (pinfunction "PB0_18") (pintype "bidirectional"))
    )
    (net (code "168") (name "~{DW_SPI_CS}") (class "Default")
      (node (ref "U1") (pin "24") (pinfunction "~{SPICS}_24") (pintype "input"))
      (node (ref "U10") (pin "14") (pinfunction "PA4_14") (pintype "bidirectional"))
    )
    (net (code "169") (name "~{FT_RST}") (class "Default")
      (node (ref "U2") (pin "18") (pinfunction "~{RESET}_18") (pintype "input"))
      (node (ref "U7") (pin "P2") (pinfunction "P1.08_P2") (pintype "bidirectional"))
    )
    (net (code "170") (name "~{NRF_CS_IMU}") (class "Default")
      (node (ref "U3") (pin "2") (pinfunction "CS_2") (pintype "bidirectional"))
      (node (ref "U7") (pin "AC11") (pinfunction "P0.16_AC11") (pintype "bidirectional"))
    )
    (net (code "171") (name "~{NRF_CS_SD}") (class "Default")
      (node (ref "J2") (pin "2") (pinfunction "DATA3-CD/CS_N_2") (pintype "bidirectional"))
      (node (ref "R13") (pin "1") (pinfunction "1_1") (pintype "passive"))
      (node (ref "U7") (pin "AC13") (pinfunction "P0.18_AC13") (pintype "bidirectional"))
    )
    (net (code "172") (name "~{SD_DETECT}") (class "Default")
      (node (ref "J2") (pin "A") (pinfunction "A_A") (pintype "bidirectional"))
      (node (ref "R19") (pin "1") (pinfunction "1_1") (pintype "passive"))
      (node (ref "U7") (pin "AD22") (pinfunction "P1.00_AD22") (pintype "bidirectional"))
    )
    (net (code "173") (name "~{STM_RST}") (class "Default")
      (node (ref "J5") (pin "3") (pinfunction "~{RESET}_3") (pintype "bidirectional"))
      (node (ref "U10") (pin "7") (pinfunction "~{RST}_7") (pintype "bidirectional"))
    )
  )
)
